# 88__2.net
KiCad netlist of a schematic drawn in Altium Designer
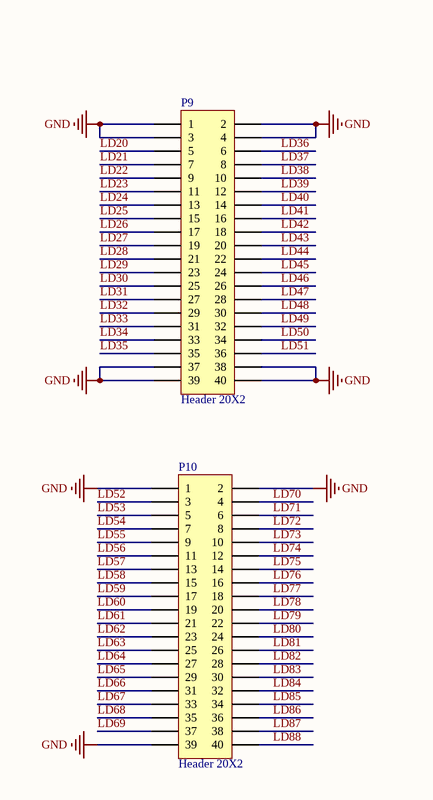
[diagram p0: 88路激光器工程_2.SchDoc, top left]
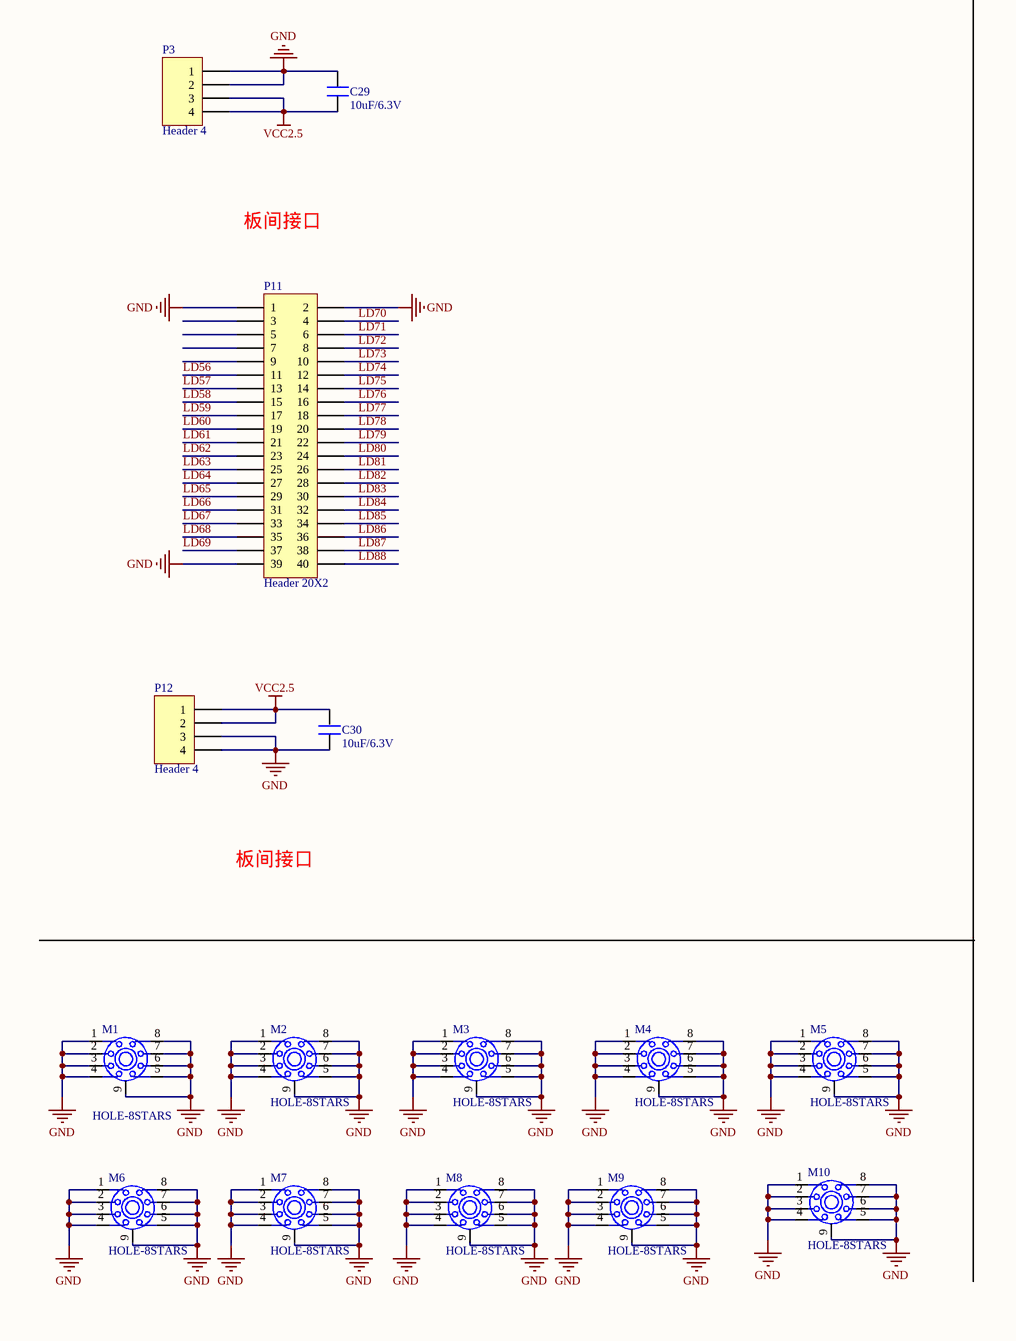
[diagram p1: 88路激光器工程_2.SchDoc, bottom left]
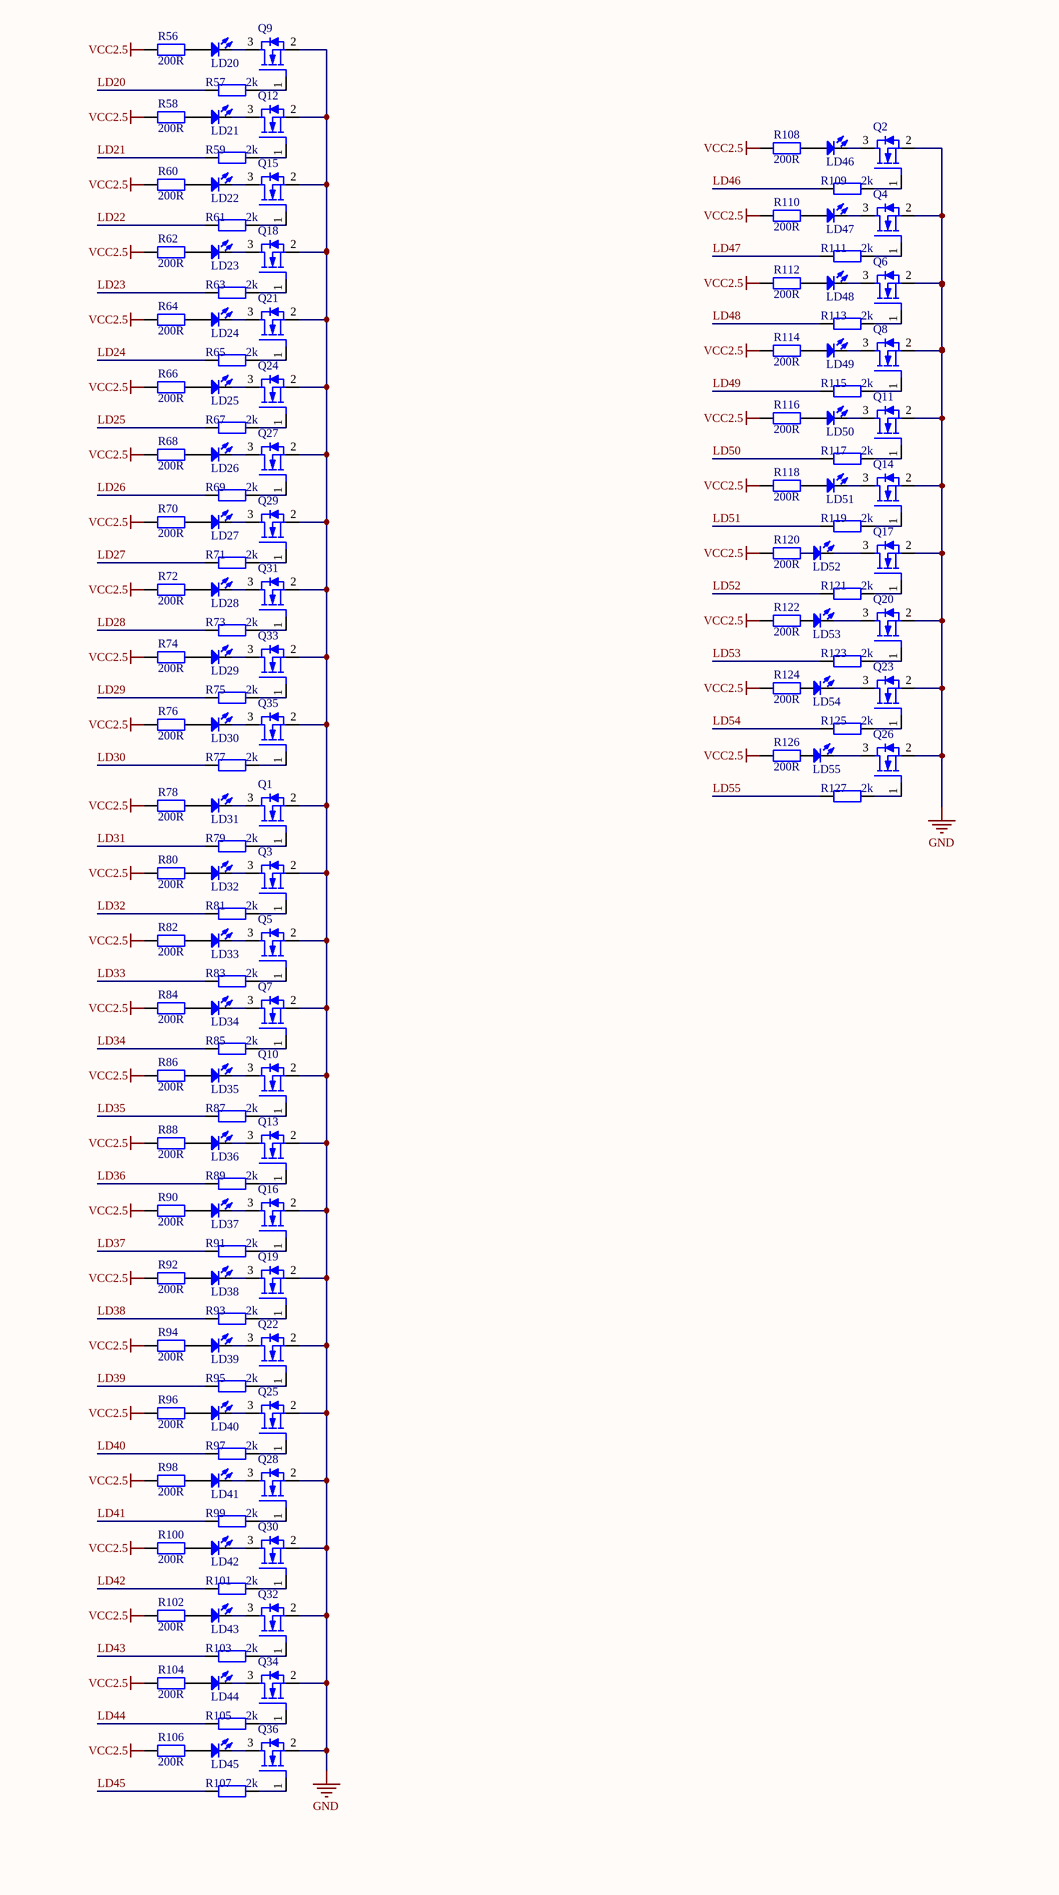
[diagram p2: 88路激光器工程_2.SchDoc, bottom right]

(export (version "E")
  (design (tool "Eeschema 10.0.6"))
  (components
    (comp (ref "C29")
      (value "10uF/6.3V")
      (footprint "C0805")
      (libsource (lib "Explorer STM32F407封装库2") (part "C"))
    )
    (comp (ref "C30")
      (value "10uF/6.3V")
      (footprint "C0805")
      (libsource (lib "Explorer STM32F407封装库2") (part "C"))
    )
    (comp (ref "LD20") (value "LD") (footprint "LD_3P") (libsource (lib "SchLib1") (part "LD")))
    (comp (ref "LD21") (value "LD") (footprint "LD_3P") (libsource (lib "SchLib1") (part "LD")))
    (comp (ref "LD22") (value "LD") (footprint "LD_3P") (libsource (lib "SchLib1") (part "LD")))
    (comp (ref "LD23") (value "LD") (footprint "LD_3P") (libsource (lib "SchLib1") (part "LD")))
    (comp (ref "LD24") (value "LD") (footprint "LD_3P") (libsource (lib "SchLib1") (part "LD")))
    (comp (ref "LD25") (value "LD") (footprint "LD_3P") (libsource (lib "SchLib1") (part "LD")))
    (comp (ref "LD26") (value "LD") (footprint "LD_3P") (libsource (lib "SchLib1") (part "LD")))
    (comp (ref "LD27") (value "LD") (footprint "LD_3P") (libsource (lib "SchLib1") (part "LD")))
    (comp (ref "LD28") (value "LD") (footprint "LD_3P") (libsource (lib "SchLib1") (part "LD")))
    (comp (ref "LD29") (value "LD") (footprint "LD_3P") (libsource (lib "SchLib1") (part "LD")))
    (comp (ref "LD30") (value "LD") (footprint "LD_3P") (libsource (lib "SchLib1") (part "LD")))
    (comp (ref "LD31") (value "LD") (footprint "LD_3P") (libsource (lib "SchLib1") (part "LD")))
    (comp (ref "LD32") (value "LD") (footprint "LD_3P") (libsource (lib "SchLib1") (part "LD")))
    (comp (ref "LD33") (value "LD") (footprint "LD_3P") (libsource (lib "SchLib1") (part "LD")))
    (comp (ref "LD34") (value "LD") (footprint "LD_3P") (libsource (lib "SchLib1") (part "LD")))
    (comp (ref "LD35") (value "LD") (footprint "LD_3P") (libsource (lib "SchLib1") (part "LD")))
    (comp (ref "LD36") (value "LD") (footprint "LD_3P") (libsource (lib "SchLib1") (part "LD")))
    (comp (ref "LD37") (value "LD") (footprint "LD_3P") (libsource (lib "SchLib1") (part "LD")))
    (comp (ref "LD38") (value "LD") (footprint "LD_3P") (libsource (lib "SchLib1") (part "LD")))
    (comp (ref "LD39") (value "LD") (footprint "LD_3P") (libsource (lib "SchLib1") (part "LD")))
    (comp (ref "LD40") (value "LD") (footprint "LD_3P") (libsource (lib "SchLib1") (part "LD")))
    (comp (ref "LD41") (value "LD") (footprint "LD_3P") (libsource (lib "SchLib1") (part "LD")))
    (comp (ref "LD42") (value "LD") (footprint "LD_3P") (libsource (lib "SchLib1") (part "LD")))
    (comp (ref "LD43") (value "LD") (footprint "LD_3P") (libsource (lib "SchLib1") (part "LD")))
    (comp (ref "LD44") (value "LD") (footprint "LD_3P") (libsource (lib "SchLib1") (part "LD")))
    (comp (ref "LD45") (value "LD") (footprint "LD_3P") (libsource (lib "SchLib1") (part "LD")))
    (comp (ref "LD46") (value "LD") (footprint "LD_3P") (libsource (lib "SchLib1") (part "LD")))
    (comp (ref "LD47") (value "LD") (footprint "LD_3P") (libsource (lib "SchLib1") (part "LD")))
    (comp (ref "LD48") (value "LD") (footprint "LD_3P") (libsource (lib "SchLib1") (part "LD")))
    (comp (ref "LD49") (value "LD") (footprint "LD_3P") (libsource (lib "SchLib1") (part "LD")))
    (comp (ref "LD50") (value "LD") (footprint "LD_3P") (libsource (lib "SchLib1") (part "LD")))
    (comp (ref "LD51") (value "LD") (footprint "LD_3P") (libsource (lib "SchLib1") (part "LD")))
    (comp (ref "LD52") (value "LD") (footprint "LD_3P") (libsource (lib "SchLib1") (part "LD")))
    (comp (ref "LD53") (value "LD") (footprint "LD_3P") (libsource (lib "SchLib1") (part "LD")))
    (comp (ref "LD54") (value "LD") (footprint "LD_3P") (libsource (lib "SchLib1") (part "LD")))
    (comp (ref "LD55") (value "LD") (footprint "LD_3P") (libsource (lib "SchLib1") (part "LD")))
    (comp (ref "M1")
      (value "HOLE-8STARS")
      (footprint "HOLE_3MM")
      (libsource (lib "TOF_SCH") (part "HOLE-8STARS"))
    )
    (comp (ref "M2")
      (value "HOLE-8STARS")
      (footprint "HOLE_3MM")
      (libsource (lib "TOF_SCH") (part "HOLE-8STARS"))
    )
    (comp (ref "M3")
      (value "HOLE-8STARS")
      (footprint "HOLE_3MM")
      (libsource (lib "TOF_SCH") (part "HOLE-8STARS"))
    )
    (comp (ref "M4")
      (value "HOLE-8STARS")
      (footprint "HOLE_3MM")
      (libsource (lib "TOF_SCH") (part "HOLE-8STARS"))
    )
    (comp (ref "M5")
      (value "HOLE-8STARS")
      (footprint "HOLE_3MM")
      (libsource (lib "TOF_SCH") (part "HOLE-8STARS"))
    )
    (comp (ref "M6")
      (value "HOLE-8STARS")
      (footprint "HOLE_3MM")
      (libsource (lib "TOF_SCH") (part "HOLE-8STARS"))
    )
    (comp (ref "M7")
      (value "HOLE-8STARS")
      (footprint "HOLE_3MM")
      (libsource (lib "TOF_SCH") (part "HOLE-8STARS"))
    )
    (comp (ref "M8")
      (value "HOLE-8STARS")
      (footprint "HOLE_3MM")
      (libsource (lib "TOF_SCH") (part "HOLE-8STARS"))
    )
    (comp (ref "M9")
      (value "HOLE-8STARS")
      (footprint "HOLE_3MM")
      (libsource (lib "TOF_SCH") (part "HOLE-8STARS"))
    )
    (comp (ref "M10")
      (value "HOLE-8STARS")
      (footprint "HOLE_3MM")
      (libsource (lib "TOF_SCH") (part "HOLE-8STARS"))
    )
    (comp (ref "P3")
      (value "Header 4")
      (footprint "XH2.54MM_4P_立式")
      (description "Header, 4-Pin")
      (fields (field (name "PUBLISHER") "Altium Limited"))
      (libsource (lib "Miscellaneous Connectors") (part "Header 4"))
    )
    (comp (ref "P9")
      (value "Header 20X2")
      (footprint "JATG_2.0mm_2x20P_SMD")
      (description "Header, 20-Pin, Dual row")
      (fields (field (name "PUBLISHER") "Altium Limited"))
      (libsource (lib "Miscellaneous Connectors") (part "Header 20X2"))
    )
    (comp (ref "P10")
      (value "Header 20X2")
      (footprint "JATG_2.0mm_2x20P_SMD")
      (description "Header, 20-Pin, Dual row")
      (fields (field (name "PUBLISHER") "Altium Limited"))
      (libsource (lib "Miscellaneous Connectors") (part "Header 20X2"))
    )
    (comp (ref "P11")
      (value "Header 20X2")
      (footprint "JATG_2.0mm_2x20P_SMD")
      (description "Header, 20-Pin, Dual row")
      (fields (field (name "PUBLISHER") "Altium Limited"))
      (libsource (lib "Miscellaneous Connectors") (part "Header 20X2"))
    )
    (comp (ref "P12")
      (value "Header 4")
      (footprint "XH2.54MM_4P_立式")
      (description "Header, 4-Pin")
      (fields (field (name "PUBLISHER") "Altium Limited"))
      (libsource (lib "Miscellaneous Connectors") (part "Header 4"))
    )
    (comp (ref "Q1") (value "NMOS") (footprint "SOT23-3") (libsource (lib "88路激光器工程") (part "NMOS")))
    (comp (ref "Q2") (value "NMOS") (footprint "SOT23-3") (libsource (lib "88路激光器工程") (part "NMOS")))
    (comp (ref "Q3") (value "NMOS") (footprint "SOT23-3") (libsource (lib "88路激光器工程") (part "NMOS")))
    (comp (ref "Q4") (value "NMOS") (footprint "SOT23-3") (libsource (lib "88路激光器工程") (part "NMOS")))
    (comp (ref "Q5") (value "NMOS") (footprint "SOT23-3") (libsource (lib "88路激光器工程") (part "NMOS")))
    (comp (ref "Q6") (value "NMOS") (footprint "SOT23-3") (libsource (lib "88路激光器工程") (part "NMOS")))
    (comp (ref "Q7") (value "NMOS") (footprint "SOT23-3") (libsource (lib "88路激光器工程") (part "NMOS")))
    (comp (ref "Q8") (value "NMOS") (footprint "SOT23-3") (libsource (lib "88路激光器工程") (part "NMOS")))
    (comp (ref "Q9") (value "NMOS") (footprint "SOT23-3") (libsource (lib "88路激光器工程") (part "NMOS")))
    (comp (ref "Q10") (value "NMOS") (footprint "SOT23-3") (libsource (lib "88路激光器工程") (part "NMOS")))
    (comp (ref "Q11") (value "NMOS") (footprint "SOT23-3") (libsource (lib "88路激光器工程") (part "NMOS")))
    (comp (ref "Q12") (value "NMOS") (footprint "SOT23-3") (libsource (lib "88路激光器工程") (part "NMOS")))
    (comp (ref "Q13") (value "NMOS") (footprint "SOT23-3") (libsource (lib "88路激光器工程") (part "NMOS")))
    (comp (ref "Q14") (value "NMOS") (footprint "SOT23-3") (libsource (lib "88路激光器工程") (part "NMOS")))
    (comp (ref "Q15") (value "NMOS") (footprint "SOT23-3") (libsource (lib "88路激光器工程") (part "NMOS")))
    (comp (ref "Q16") (value "NMOS") (footprint "SOT23-3") (libsource (lib "88路激光器工程") (part "NMOS")))
    (comp (ref "Q17") (value "NMOS") (footprint "SOT23-3") (libsource (lib "88路激光器工程") (part "NMOS")))
    (comp (ref "Q18") (value "NMOS") (footprint "SOT23-3") (libsource (lib "88路激光器工程") (part "NMOS")))
    (comp (ref "Q19") (value "NMOS") (footprint "SOT23-3") (libsource (lib "88路激光器工程") (part "NMOS")))
    (comp (ref "Q20") (value "NMOS") (footprint "SOT23-3") (libsource (lib "88路激光器工程") (part "NMOS")))
    (comp (ref "Q21") (value "NMOS") (footprint "SOT23-3") (libsource (lib "88路激光器工程") (part "NMOS")))
    (comp (ref "Q22") (value "NMOS") (footprint "SOT23-3") (libsource (lib "88路激光器工程") (part "NMOS")))
    (comp (ref "Q23") (value "NMOS") (footprint "SOT23-3") (libsource (lib "88路激光器工程") (part "NMOS")))
    (comp (ref "Q24") (value "NMOS") (footprint "SOT23-3") (libsource (lib "88路激光器工程") (part "NMOS")))
    (comp (ref "Q25") (value "NMOS") (footprint "SOT23-3") (libsource (lib "88路激光器工程") (part "NMOS")))
    (comp (ref "Q26") (value "NMOS") (footprint "SOT23-3") (libsource (lib "88路激光器工程") (part "NMOS")))
    (comp (ref "Q27") (value "NMOS") (footprint "SOT23-3") (libsource (lib "88路激光器工程") (part "NMOS")))
    (comp (ref "Q28") (value "NMOS") (footprint "SOT23-3") (libsource (lib "88路激光器工程") (part "NMOS")))
    (comp (ref "Q29") (value "NMOS") (footprint "SOT23-3") (libsource (lib "88路激光器工程") (part "NMOS")))
    (comp (ref "Q30") (value "NMOS") (footprint "SOT23-3") (libsource (lib "88路激光器工程") (part "NMOS")))
    (comp (ref "Q31") (value "NMOS") (footprint "SOT23-3") (libsource (lib "88路激光器工程") (part "NMOS")))
    (comp (ref "Q32") (value "NMOS") (footprint "SOT23-3") (libsource (lib "88路激光器工程") (part "NMOS")))
    (comp (ref "Q33") (value "NMOS") (footprint "SOT23-3") (libsource (lib "88路激光器工程") (part "NMOS")))
    (comp (ref "Q34") (value "NMOS") (footprint "SOT23-3") (libsource (lib "88路激光器工程") (part "NMOS")))
    (comp (ref "Q35") (value "NMOS") (footprint "SOT23-3") (libsource (lib "88路激光器工程") (part "NMOS")))
    (comp (ref "Q36") (value "NMOS") (footprint "SOT23-3") (libsource (lib "88路激光器工程") (part "NMOS")))
    (comp (ref "R56")
      (value "200R")
      (footprint "R0805")
      (description "Resistor")
      (fields (field (name "PUBLISHER") "Altium Limited"))
      (libsource (lib "Miscellaneous Devices") (part "Res2"))
    )
    (comp (ref "R57")
      (value "2k")
      (footprint "R0805")
      (description "Resistor")
      (fields (field (name "PUBLISHER") "Altium Limited"))
      (libsource (lib "Miscellaneous Devices") (part "Res2"))
    )
    (comp (ref "R58")
      (value "200R")
      (footprint "R0805")
      (description "Resistor")
      (fields (field (name "PUBLISHER") "Altium Limited"))
      (libsource (lib "Miscellaneous Devices") (part "Res2"))
    )
    (comp (ref "R59")
      (value "2k")
      (footprint "R0805")
      (description "Resistor")
      (fields (field (name "PUBLISHER") "Altium Limited"))
      (libsource (lib "Miscellaneous Devices") (part "Res2"))
    )
    (comp (ref "R60")
      (value "200R")
      (footprint "R0805")
      (description "Resistor")
      (fields (field (name "PUBLISHER") "Altium Limited"))
      (libsource (lib "Miscellaneous Devices") (part "Res2"))
    )
    (comp (ref "R61")
      (value "2k")
      (footprint "R0805")
      (description "Resistor")
      (fields (field (name "PUBLISHER") "Altium Limited"))
      (libsource (lib "Miscellaneous Devices") (part "Res2"))
    )
    (comp (ref "R62")
      (value "200R")
      (footprint "R0805")
      (description "Resistor")
      (fields (field (name "PUBLISHER") "Altium Limited"))
      (libsource (lib "Miscellaneous Devices") (part "Res2"))
    )
    (comp (ref "R63")
      (value "2k")
      (footprint "R0805")
      (description "Resistor")
      (fields (field (name "PUBLISHER") "Altium Limited"))
      (libsource (lib "Miscellaneous Devices") (part "Res2"))
    )
    (comp (ref "R64")
      (value "200R")
      (footprint "R0805")
      (description "Resistor")
      (fields (field (name "PUBLISHER") "Altium Limited"))
      (libsource (lib "Miscellaneous Devices") (part "Res2"))
    )
    (comp (ref "R65")
      (value "2k")
      (footprint "R0805")
      (description "Resistor")
      (fields (field (name "PUBLISHER") "Altium Limited"))
      (libsource (lib "Miscellaneous Devices") (part "Res2"))
    )
    (comp (ref "R66")
      (value "200R")
      (footprint "R0805")
      (description "Resistor")
      (fields (field (name "PUBLISHER") "Altium Limited"))
      (libsource (lib "Miscellaneous Devices") (part "Res2"))
    )
    (comp (ref "R67")
      (value "2k")
      (footprint "R0805")
      (description "Resistor")
      (fields (field (name "PUBLISHER") "Altium Limited"))
      (libsource (lib "Miscellaneous Devices") (part "Res2"))
    )
    (comp (ref "R68")
      (value "200R")
      (footprint "R0805")
      (description "Resistor")
      (fields (field (name "PUBLISHER") "Altium Limited"))
      (libsource (lib "Miscellaneous Devices") (part "Res2"))
    )
    (comp (ref "R69")
      (value "2k")
      (footprint "R0805")
      (description "Resistor")
      (fields (field (name "PUBLISHER") "Altium Limited"))
      (libsource (lib "Miscellaneous Devices") (part "Res2"))
    )
    (comp (ref "R70")
      (value "200R")
      (footprint "R0805")
      (description "Resistor")
      (fields (field (name "PUBLISHER") "Altium Limited"))
      (libsource (lib "Miscellaneous Devices") (part "Res2"))
    )
    (comp (ref "R71")
      (value "2k")
      (footprint "R0805")
      (description "Resistor")
      (fields (field (name "PUBLISHER") "Altium Limited"))
      (libsource (lib "Miscellaneous Devices") (part "Res2"))
    )
    (comp (ref "R72")
      (value "200R")
      (footprint "R0805")
      (description "Resistor")
      (fields (field (name "PUBLISHER") "Altium Limited"))
      (libsource (lib "Miscellaneous Devices") (part "Res2"))
    )
    (comp (ref "R73")
      (value "2k")
      (footprint "R0805")
      (description "Resistor")
      (fields (field (name "PUBLISHER") "Altium Limited"))
      (libsource (lib "Miscellaneous Devices") (part "Res2"))
    )
    (comp (ref "R74")
      (value "200R")
      (footprint "R0805")
      (description "Resistor")
      (fields (field (name "PUBLISHER") "Altium Limited"))
      (libsource (lib "Miscellaneous Devices") (part "Res2"))
    )
    (comp (ref "R75")
      (value "2k")
      (footprint "R0805")
      (description "Resistor")
      (fields (field (name "PUBLISHER") "Altium Limited"))
      (libsource (lib "Miscellaneous Devices") (part "Res2"))
    )
    (comp (ref "R76")
      (value "200R")
      (footprint "R0805")
      (description "Resistor")
      (fields (field (name "PUBLISHER") "Altium Limited"))
      (libsource (lib "Miscellaneous Devices") (part "Res2"))
    )
    (comp (ref "R77")
      (value "2k")
      (footprint "R0805")
      (description "Resistor")
      (fields (field (name "PUBLISHER") "Altium Limited"))
      (libsource (lib "Miscellaneous Devices") (part "Res2"))
    )
    (comp (ref "R78")
      (value "200R")
      (footprint "R0805")
      (description "Resistor")
      (fields (field (name "PUBLISHER") "Altium Limited"))
      (libsource (lib "Miscellaneous Devices") (part "Res2"))
    )
    (comp (ref "R79")
      (value "2k")
      (footprint "R0805")
      (description "Resistor")
      (fields (field (name "PUBLISHER") "Altium Limited"))
      (libsource (lib "Miscellaneous Devices") (part "Res2"))
    )
    (comp (ref "R80")
      (value "200R")
      (footprint "R0805")
      (description "Resistor")
      (fields (field (name "PUBLISHER") "Altium Limited"))
      (libsource (lib "Miscellaneous Devices") (part "Res2"))
    )
    (comp (ref "R81")
      (value "2k")
      (footprint "R0805")
      (description "Resistor")
      (fields (field (name "PUBLISHER") "Altium Limited"))
      (libsource (lib "Miscellaneous Devices") (part "Res2"))
    )
    (comp (ref "R82")
      (value "200R")
      (footprint "R0805")
      (description "Resistor")
      (fields (field (name "PUBLISHER") "Altium Limited"))
      (libsource (lib "Miscellaneous Devices") (part "Res2"))
    )
    (comp (ref "R83")
      (value "2k")
      (footprint "R0805")
      (description "Resistor")
      (fields (field (name "PUBLISHER") "Altium Limited"))
      (libsource (lib "Miscellaneous Devices") (part "Res2"))
    )
    (comp (ref "R84")
      (value "200R")
      (footprint "R0805")
      (description "Resistor")
      (fields (field (name "PUBLISHER") "Altium Limited"))
      (libsource (lib "Miscellaneous Devices") (part "Res2"))
    )
    (comp (ref "R85")
      (value "2k")
      (footprint "R0805")
      (description "Resistor")
      (fields (field (name "PUBLISHER") "Altium Limited"))
      (libsource (lib "Miscellaneous Devices") (part "Res2"))
    )
    (comp (ref "R86")
      (value "200R")
      (footprint "R0805")
      (description "Resistor")
      (fields (field (name "PUBLISHER") "Altium Limited"))
      (libsource (lib "Miscellaneous Devices") (part "Res2"))
    )
    (comp (ref "R87")
      (value "2k")
      (footprint "R0805")
      (description "Resistor")
      (fields (field (name "PUBLISHER") "Altium Limited"))
      (libsource (lib "Miscellaneous Devices") (part "Res2"))
    )
    (comp (ref "R88")
      (value "200R")
      (footprint "R0805")
      (description "Resistor")
      (fields (field (name "PUBLISHER") "Altium Limited"))
      (libsource (lib "Miscellaneous Devices") (part "Res2"))
    )
    (comp (ref "R89")
      (value "2k")
      (footprint "R0805")
      (description "Resistor")
      (fields (field (name "PUBLISHER") "Altium Limited"))
      (libsource (lib "Miscellaneous Devices") (part "Res2"))
    )
    (comp (ref "R90")
      (value "200R")
      (footprint "R0805")
      (description "Resistor")
      (fields (field (name "PUBLISHER") "Altium Limited"))
      (libsource (lib "Miscellaneous Devices") (part "Res2"))
    )
    (comp (ref "R91")
      (value "2k")
      (footprint "R0805")
      (description "Resistor")
      (fields (field (name "PUBLISHER") "Altium Limited"))
      (libsource (lib "Miscellaneous Devices") (part "Res2"))
    )
    (comp (ref "R92")
      (value "200R")
      (footprint "R0805")
      (description "Resistor")
      (fields (field (name "PUBLISHER") "Altium Limited"))
      (libsource (lib "Miscellaneous Devices") (part "Res2"))
    )
    (comp (ref "R93")
      (value "2k")
      (footprint "R0805")
      (description "Resistor")
      (fields (field (name "PUBLISHER") "Altium Limited"))
      (libsource (lib "Miscellaneous Devices") (part "Res2"))
    )
    (comp (ref "R94")
      (value "200R")
      (footprint "R0805")
      (description "Resistor")
      (fields (field (name "PUBLISHER") "Altium Limited"))
      (libsource (lib "Miscellaneous Devices") (part "Res2"))
    )
    (comp (ref "R95")
      (value "2k")
      (footprint "R0805")
      (description "Resistor")
      (fields (field (name "PUBLISHER") "Altium Limited"))
      (libsource (lib "Miscellaneous Devices") (part "Res2"))
    )
    (comp (ref "R96")
      (value "200R")
      (footprint "R0805")
      (description "Resistor")
      (fields (field (name "PUBLISHER") "Altium Limited"))
      (libsource (lib "Miscellaneous Devices") (part "Res2"))
    )
    (comp (ref "R97")
      (value "2k")
      (footprint "R0805")
      (description "Resistor")
      (fields (field (name "PUBLISHER") "Altium Limited"))
      (libsource (lib "Miscellaneous Devices") (part "Res2"))
    )
    (comp (ref "R98")
      (value "200R")
      (footprint "R0805")
      (description "Resistor")
      (fields (field (name "PUBLISHER") "Altium Limited"))
      (libsource (lib "Miscellaneous Devices") (part "Res2"))
    )
    (comp (ref "R99")
      (value "2k")
      (footprint "R0805")
      (description "Resistor")
      (fields (field (name "PUBLISHER") "Altium Limited"))
      (libsource (lib "Miscellaneous Devices") (part "Res2"))
    )
    (comp (ref "R100")
      (value "200R")
      (footprint "R0805")
      (description "Resistor")
      (fields (field (name "PUBLISHER") "Altium Limited"))
      (libsource (lib "Miscellaneous Devices") (part "Res2"))
    )
    (comp (ref "R101")
      (value "2k")
      (footprint "R0805")
      (description "Resistor")
      (fields (field (name "PUBLISHER") "Altium Limited"))
      (libsource (lib "Miscellaneous Devices") (part "Res2"))
    )
    (comp (ref "R102")
      (value "200R")
      (footprint "R0805")
      (description "Resistor")
      (fields (field (name "PUBLISHER") "Altium Limited"))
      (libsource (lib "Miscellaneous Devices") (part "Res2"))
    )
    (comp (ref "R103")
      (value "2k")
      (footprint "R0805")
      (description "Resistor")
      (fields (field (name "PUBLISHER") "Altium Limited"))
      (libsource (lib "Miscellaneous Devices") (part "Res2"))
    )
    (comp (ref "R104")
      (value "200R")
      (footprint "R0805")
      (description "Resistor")
      (fields (field (name "PUBLISHER") "Altium Limited"))
      (libsource (lib "Miscellaneous Devices") (part "Res2"))
    )
    (comp (ref "R105")
      (value "2k")
      (footprint "R0805")
      (description "Resistor")
      (fields (field (name "PUBLISHER") "Altium Limited"))
      (libsource (lib "Miscellaneous Devices") (part "Res2"))
    )
    (comp (ref "R106")
      (value "200R")
      (footprint "R0805")
      (description "Resistor")
      (fields (field (name "PUBLISHER") "Altium Limited"))
      (libsource (lib "Miscellaneous Devices") (part "Res2"))
    )
    (comp (ref "R107")
      (value "2k")
      (footprint "R0805")
      (description "Resistor")
      (fields (field (name "PUBLISHER") "Altium Limited"))
      (libsource (lib "Miscellaneous Devices") (part "Res2"))
    )
    (comp (ref "R108")
      (value "200R")
      (footprint "R0805")
      (description "Resistor")
      (fields (field (name "PUBLISHER") "Altium Limited"))
      (libsource (lib "Miscellaneous Devices") (part "Res2"))
    )
    (comp (ref "R109")
      (value "2k")
      (footprint "R0805")
      (description "Resistor")
      (fields (field (name "PUBLISHER") "Altium Limited"))
      (libsource (lib "Miscellaneous Devices") (part "Res2"))
    )
    (comp (ref "R110")
      (value "200R")
      (footprint "R0805")
      (description "Resistor")
      (fields (field (name "PUBLISHER") "Altium Limited"))
      (libsource (lib "Miscellaneous Devices") (part "Res2"))
    )
    (comp (ref "R111")
      (value "2k")
      (footprint "R0805")
      (description "Resistor")
      (fields (field (name "PUBLISHER") "Altium Limited"))
      (libsource (lib "Miscellaneous Devices") (part "Res2"))
    )
    (comp (ref "R112")
      (value "200R")
      (footprint "R0805")
      (description "Resistor")
      (fields (field (name "PUBLISHER") "Altium Limited"))
      (libsource (lib "Miscellaneous Devices") (part "Res2"))
    )
    (comp (ref "R113")
      (value "2k")
      (footprint "R0805")
      (description "Resistor")
      (fields (field (name "PUBLISHER") "Altium Limited"))
      (libsource (lib "Miscellaneous Devices") (part "Res2"))
    )
    (comp (ref "R114")
      (value "200R")
      (footprint "R0805")
      (description "Resistor")
      (fields (field (name "PUBLISHER") "Altium Limited"))
      (libsource (lib "Miscellaneous Devices") (part "Res2"))
    )
    (comp (ref "R115")
      (value "2k")
      (footprint "R0805")
      (description "Resistor")
      (fields (field (name "PUBLISHER") "Altium Limited"))
      (libsource (lib "Miscellaneous Devices") (part "Res2"))
    )
    (comp (ref "R116")
      (value "200R")
      (footprint "R0805")
      (description "Resistor")
      (fields (field (name "PUBLISHER") "Altium Limited"))
      (libsource (lib "Miscellaneous Devices") (part "Res2"))
    )
    (comp (ref "R117")
      (value "2k")
      (footprint "R0805")
      (description "Resistor")
      (fields (field (name "PUBLISHER") "Altium Limited"))
      (libsource (lib "Miscellaneous Devices") (part "Res2"))
    )
    (comp (ref "R118")
      (value "200R")
      (footprint "R0805")
      (description "Resistor")
      (fields (field (name "PUBLISHER") "Altium Limited"))
      (libsource (lib "Miscellaneous Devices") (part "Res2"))
    )
    (comp (ref "R119")
      (value "2k")
      (footprint "R0805")
      (description "Resistor")
      (fields (field (name "PUBLISHER") "Altium Limited"))
      (libsource (lib "Miscellaneous Devices") (part "Res2"))
    )
    (comp (ref "R120")
      (value "200R")
      (footprint "R0805")
      (description "Resistor")
      (fields (field (name "PUBLISHER") "Altium Limited"))
      (libsource (lib "Miscellaneous Devices") (part "Res2"))
    )
    (comp (ref "R121")
      (value "2k")
      (footprint "R0805")
      (description "Resistor")
      (fields (field (name "PUBLISHER") "Altium Limited"))
      (libsource (lib "Miscellaneous Devices") (part "Res2"))
    )
    (comp (ref "R122")
      (value "200R")
      (footprint "R0805")
      (description "Resistor")
      (fields (field (name "PUBLISHER") "Altium Limited"))
      (libsource (lib "Miscellaneous Devices") (part "Res2"))
    )
    (comp (ref "R123")
      (value "2k")
      (footprint "R0805")
      (description "Resistor")
      (fields (field (name "PUBLISHER") "Altium Limited"))
      (libsource (lib "Miscellaneous Devices") (part "Res2"))
    )
    (comp (ref "R124")
      (value "200R")
      (footprint "R0805")
      (description "Resistor")
      (fields (field (name "PUBLISHER") "Altium Limited"))
      (libsource (lib "Miscellaneous Devices") (part "Res2"))
    )
    (comp (ref "R125")
      (value "2k")
      (footprint "R0805")
      (description "Resistor")
      (fields (field (name "PUBLISHER") "Altium Limited"))
      (libsource (lib "Miscellaneous Devices") (part "Res2"))
    )
    (comp (ref "R126")
      (value "200R")
      (footprint "R0805")
      (description "Resistor")
      (fields (field (name "PUBLISHER") "Altium Limited"))
      (libsource (lib "Miscellaneous Devices") (part "Res2"))
    )
    (comp (ref "R127")
      (value "2k")
      (footprint "R0805")
      (description "Resistor")
      (fields (field (name "PUBLISHER") "Altium Limited"))
      (libsource (lib "Miscellaneous Devices") (part "Res2"))
    )
  )
  (nets
    (net (code "1") (name "/LD20") (class "Default")
      (node (ref "P9") (pin "5") (pinfunction "5_5") (pintype "passive"))
      (node (ref "R57") (pin "2") (pinfunction "2_2") (pintype "passive"))
    )
    (net (code "2") (name "/LD21") (class "Default")
      (node (ref "P9") (pin "7") (pinfunction "7_7") (pintype "passive"))
      (node (ref "R59") (pin "2") (pinfunction "2_2") (pintype "passive"))
    )
    (net (code "3") (name "/LD22") (class "Default")
      (node (ref "P9") (pin "9") (pinfunction "9_9") (pintype "passive"))
      (node (ref "R61") (pin "2") (pinfunction "2_2") (pintype "passive"))
    )
    (net (code "4") (name "/LD23") (class "Default")
      (node (ref "P9") (pin "11") (pinfunction "11_11") (pintype "passive"))
      (node (ref "R63") (pin "2") (pinfunction "2_2") (pintype "passive"))
    )
    (net (code "5") (name "/LD24") (class "Default")
      (node (ref "P9") (pin "13") (pinfunction "13_13") (pintype "passive"))
      (node (ref "R65") (pin "2") (pinfunction "2_2") (pintype "passive"))
    )
    (net (code "6") (name "/LD25") (class "Default")
      (node (ref "P9") (pin "15") (pinfunction "15_15") (pintype "passive"))
      (node (ref "R67") (pin "2") (pinfunction "2_2") (pintype "passive"))
    )
    (net (code "7") (name "/LD26") (class "Default")
      (node (ref "P9") (pin "17") (pinfunction "17_17") (pintype "passive"))
      (node (ref "R69") (pin "2") (pinfunction "2_2") (pintype "passive"))
    )
    (net (code "8") (name "/LD27") (class "Default")
      (node (ref "P9") (pin "19") (pinfunction "19_19") (pintype "passive"))
      (node (ref "R71") (pin "2") (pinfunction "2_2") (pintype "passive"))
    )
    (net (code "9") (name "/LD28") (class "Default")
      (node (ref "P9") (pin "21") (pinfunction "21_21") (pintype "passive"))
      (node (ref "R73") (pin "2") (pinfunction "2_2") (pintype "passive"))
    )
    (net (code "10") (name "/LD29") (class "Default")
      (node (ref "P9") (pin "23") (pinfunction "23_23") (pintype "passive"))
      (node (ref "R75") (pin "2") (pinfunction "2_2") (pintype "passive"))
    )
    (net (code "11") (name "/LD30") (class "Default")
      (node (ref "P9") (pin "25") (pinfunction "25_25") (pintype "passive"))
      (node (ref "R77") (pin "2") (pinfunction "2_2") (pintype "passive"))
    )
    (net (code "12") (name "/LD31") (class "Default")
      (node (ref "P9") (pin "27") (pinfunction "27_27") (pintype "passive"))
      (node (ref "R79") (pin "2") (pinfunction "2_2") (pintype "passive"))
    )
    (net (code "13") (name "/LD32") (class "Default")
      (node (ref "P9") (pin "29") (pinfunction "29_29") (pintype "passive"))
      (node (ref "R81") (pin "2") (pinfunction "2_2") (pintype "passive"))
    )
    (net (code "14") (name "/LD33") (class "Default")
      (node (ref "P9") (pin "31") (pinfunction "31_31") (pintype "passive"))
      (node (ref "R83") (pin "2") (pinfunction "2_2") (pintype "passive"))
    )
    (net (code "15") (name "/LD34") (class "Default")
      (node (ref "P9") (pin "33") (pinfunction "33_33") (pintype "passive"))
      (node (ref "R85") (pin "2") (pinfunction "2_2") (pintype "passive"))
    )
    (net (code "16") (name "/LD35") (class "Default")
      (node (ref "P9") (pin "35") (pinfunction "35_35") (pintype "passive"))
      (node (ref "R87") (pin "2") (pinfunction "2_2") (pintype "passive"))
    )
    (net (code "17") (name "/LD36") (class "Default")
      (node (ref "P9") (pin "6") (pinfunction "6_6") (pintype "passive"))
      (node (ref "R89") (pin "2") (pinfunction "2_2") (pintype "passive"))
    )
    (net (code "18") (name "/LD37") (class "Default")
      (node (ref "P9") (pin "8") (pinfunction "8_8") (pintype "passive"))
      (node (ref "R91") (pin "2") (pinfunction "2_2") (pintype "passive"))
    )
    (net (code "19") (name "/LD38") (class "Default")
      (node (ref "P9") (pin "10") (pinfunction "10_10") (pintype "passive"))
      (node (ref "R93") (pin "2") (pinfunction "2_2") (pintype "passive"))
    )
    (net (code "20") (name "/LD39") (class "Default")
      (node (ref "P9") (pin "12") (pinfunction "12_12") (pintype "passive"))
      (node (ref "R95") (pin "2") (pinfunction "2_2") (pintype "passive"))
    )
    (net (code "21") (name "/LD40") (class "Default")
      (node (ref "P9") (pin "14") (pinfunction "14_14") (pintype "passive"))
      (node (ref "R97") (pin "2") (pinfunction "2_2") (pintype "passive"))
    )
    (net (code "22") (name "/LD41") (class "Default")
      (node (ref "P9") (pin "16") (pinfunction "16_16") (pintype "passive"))
      (node (ref "R99") (pin "2") (pinfunction "2_2") (pintype "passive"))
    )
    (net (code "23") (name "/LD42") (class "Default")
      (node (ref "P9") (pin "18") (pinfunction "18_18") (pintype "passive"))
      (node (ref "R101") (pin "2") (pinfunction "2_2") (pintype "passive"))
    )
    (net (code "24") (name "/LD43") (class "Default")
      (node (ref "P9") (pin "20") (pinfunction "20_20") (pintype "passive"))
      (node (ref "R103") (pin "2") (pinfunction "2_2") (pintype "passive"))
    )
    (net (code "25") (name "/LD44") (class "Default")
      (node (ref "P9") (pin "22") (pinfunction "22_22") (pintype "passive"))
      (node (ref "R105") (pin "2") (pinfunction "2_2") (pintype "passive"))
    )
    (net (code "26") (name "/LD45") (class "Default")
      (node (ref "P9") (pin "24") (pinfunction "24_24") (pintype "passive"))
      (node (ref "R107") (pin "2") (pinfunction "2_2") (pintype "passive"))
    )
    (net (code "27") (name "/LD46") (class "Default")
      (node (ref "P9") (pin "26") (pinfunction "26_26") (pintype "passive"))
      (node (ref "R109") (pin "2") (pinfunction "2_2") (pintype "passive"))
    )
    (net (code "28") (name "/LD47") (class "Default")
      (node (ref "P9") (pin "28") (pinfunction "28_28") (pintype "passive"))
      (node (ref "R111") (pin "2") (pinfunction "2_2") (pintype "passive"))
    )
    (net (code "29") (name "/LD48") (class "Default")
      (node (ref "P9") (pin "30") (pinfunction "30_30") (pintype "passive"))
      (node (ref "R113") (pin "2") (pinfunction "2_2") (pintype "passive"))
    )
    (net (code "30") (name "/LD49") (class "Default")
      (node (ref "P9") (pin "32") (pinfunction "32_32") (pintype "passive"))
      (node (ref "R115") (pin "2") (pinfunction "2_2") (pintype "passive"))
    )
    (net (code "31") (name "/LD50") (class "Default")
      (node (ref "P9") (pin "34") (pinfunction "34_34") (pintype "passive"))
      (node (ref "R117") (pin "2") (pinfunction "2_2") (pintype "passive"))
    )
    (net (code "32") (name "/LD51") (class "Default")
      (node (ref "P9") (pin "36") (pinfunction "36_36") (pintype "passive"))
      (node (ref "R119") (pin "2") (pinfunction "2_2") (pintype "passive"))
    )
    (net (code "33") (name "/LD52") (class "Default")
      (node (ref "P10") (pin "3") (pinfunction "3_3") (pintype "passive"))
      (node (ref "R121") (pin "2") (pinfunction "2_2") (pintype "passive"))
    )
    (net (code "34") (name "/LD53") (class "Default")
      (node (ref "P10") (pin "5") (pinfunction "5_5") (pintype "passive"))
      (node (ref "R123") (pin "2") (pinfunction "2_2") (pintype "passive"))
    )
    (net (code "35") (name "/LD54") (class "Default")
      (node (ref "P10") (pin "7") (pinfunction "7_7") (pintype "passive"))
      (node (ref "R125") (pin "2") (pinfunction "2_2") (pintype "passive"))
    )
    (net (code "36") (name "/LD55") (class "Default")
      (node (ref "P10") (pin "9") (pinfunction "9_9") (pintype "passive"))
      (node (ref "R127") (pin "2") (pinfunction "2_2") (pintype "passive"))
    )
    (net (code "37") (name "/LD56") (class "Default")
      (node (ref "P10") (pin "11") (pinfunction "11_11") (pintype "passive"))
      (node (ref "P11") (pin "11") (pinfunction "11_11") (pintype "passive"))
    )
    (net (code "38") (name "/LD57") (class "Default")
      (node (ref "P10") (pin "13") (pinfunction "13_13") (pintype "passive"))
      (node (ref "P11") (pin "13") (pinfunction "13_13") (pintype "passive"))
    )
    (net (code "39") (name "/LD58") (class "Default")
      (node (ref "P10") (pin "15") (pinfunction "15_15") (pintype "passive"))
      (node (ref "P11") (pin "15") (pinfunction "15_15") (pintype "passive"))
    )
    (net (code "40") (name "/LD59") (class "Default")
      (node (ref "P10") (pin "17") (pinfunction "17_17") (pintype "passive"))
      (node (ref "P11") (pin "17") (pinfunction "17_17") (pintype "passive"))
    )
    (net (code "41") (name "/LD60") (class "Default")
      (node (ref "P10") (pin "19") (pinfunction "19_19") (pintype "passive"))
      (node (ref "P11") (pin "19") (pinfunction "19_19") (pintype "passive"))
    )
    (net (code "42") (name "/LD61") (class "Default")
      (node (ref "P10") (pin "21") (pinfunction "21_21") (pintype "passive"))
      (node (ref "P11") (pin "21") (pinfunction "21_21") (pintype "passive"))
    )
    (net (code "43") (name "/LD62") (class "Default")
      (node (ref "P10") (pin "23") (pinfunction "23_23") (pintype "passive"))
      (node (ref "P11") (pin "23") (pinfunction "23_23") (pintype "passive"))
    )
    (net (code "44") (name "/LD63") (class "Default")
      (node (ref "P10") (pin "25") (pinfunction "25_25") (pintype "passive"))
      (node (ref "P11") (pin "25") (pinfunction "25_25") (pintype "passive"))
    )
    (net (code "45") (name "/LD64") (class "Default")
      (node (ref "P10") (pin "27") (pinfunction "27_27") (pintype "passive"))
      (node (ref "P11") (pin "27") (pinfunction "27_27") (pintype "passive"))
    )
    (net (code "46") (name "/LD65") (class "Default")
      (node (ref "P10") (pin "29") (pinfunction "29_29") (pintype "passive"))
      (node (ref "P11") (pin "29") (pinfunction "29_29") (pintype "passive"))
    )
    (net (code "47") (name "/LD66") (class "Default")
      (node (ref "P10") (pin "31") (pinfunction "31_31") (pintype "passive"))
      (node (ref "P11") (pin "31") (pinfunction "31_31") (pintype "passive"))
    )
    (net (code "48") (name "/LD67") (class "Default")
      (node (ref "P10") (pin "33") (pinfunction "33_33") (pintype "passive"))
      (node (ref "P11") (pin "33") (pinfunction "33_33") (pintype "passive"))
    )
    (net (code "49") (name "/LD68") (class "Default")
      (node (ref "P10") (pin "35") (pinfunction "35_35") (pintype "passive"))
      (node (ref "P11") (pin "35") (pinfunction "35_35") (pintype "passive"))
    )
    (net (code "50") (name "/LD69") (class "Default")
      (node (ref "P10") (pin "37") (pinfunction "37_37") (pintype "passive"))
      (node (ref "P11") (pin "37") (pinfunction "37_37") (pintype "passive"))
    )
    (net (code "51") (name "/LD70") (class "Default")
      (node (ref "P10") (pin "4") (pinfunction "4_4") (pintype "passive"))
      (node (ref "P11") (pin "4") (pinfunction "4_4") (pintype "passive"))
    )
    (net (code "52") (name "/LD71") (class "Default")
      (node (ref "P10") (pin "6") (pinfunction "6_6") (pintype "passive"))
      (node (ref "P11") (pin "6") (pinfunction "6_6") (pintype "passive"))
    )
    (net (code "53") (name "/LD72") (class "Default")
      (node (ref "P10") (pin "8") (pinfunction "8_8") (pintype "passive"))
      (node (ref "P11") (pin "8") (pinfunction "8_8") (pintype "passive"))
    )
    (net (code "54") (name "/LD73") (class "Default")
      (node (ref "P10") (pin "10") (pinfunction "10_10") (pintype "passive"))
      (node (ref "P11") (pin "10") (pinfunction "10_10") (pintype "passive"))
    )
    (net (code "55") (name "/LD74") (class "Default")
      (node (ref "P10") (pin "12") (pinfunction "12_12") (pintype "passive"))
      (node (ref "P11") (pin "12") (pinfunction "12_12") (pintype "passive"))
    )
    (net (code "56") (name "/LD75") (class "Default")
      (node (ref "P10") (pin "14") (pinfunction "14_14") (pintype "passive"))
      (node (ref "P11") (pin "14") (pinfunction "14_14") (pintype "passive"))
    )
    (net (code "57") (name "/LD76") (class "Default")
      (node (ref "P10") (pin "16") (pinfunction "16_16") (pintype "passive"))
      (node (ref "P11") (pin "16") (pinfunction "16_16") (pintype "passive"))
    )
    (net (code "58") (name "/LD77") (class "Default")
      (node (ref "P10") (pin "18") (pinfunction "18_18") (pintype "passive"))
      (node (ref "P11") (pin "18") (pinfunction "18_18") (pintype "passive"))
    )
    (net (code "59") (name "/LD78") (class "Default")
      (node (ref "P10") (pin "20") (pinfunction "20_20") (pintype "passive"))
      (node (ref "P11") (pin "20") (pinfunction "20_20") (pintype "passive"))
    )
    (net (code "60") (name "/LD79") (class "Default")
      (node (ref "P10") (pin "22") (pinfunction "22_22") (pintype "passive"))
      (node (ref "P11") (pin "22") (pinfunction "22_22") (pintype "passive"))
    )
    (net (code "61") (name "/LD80") (class "Default")
      (node (ref "P10") (pin "24") (pinfunction "24_24") (pintype "passive"))
      (node (ref "P11") (pin "24") (pinfunction "24_24") (pintype "passive"))
    )
    (net (code "62") (name "/LD81") (class "Default")
      (node (ref "P10") (pin "26") (pinfunction "26_26") (pintype "passive"))
      (node (ref "P11") (pin "26") (pinfunction "26_26") (pintype "passive"))
    )
    (net (code "63") (name "/LD82") (class "Default")
      (node (ref "P10") (pin "28") (pinfunction "28_28") (pintype "passive"))
      (node (ref "P11") (pin "28") (pinfunction "28_28") (pintype "passive"))
    )
    (net (code "64") (name "/LD83") (class "Default")
      (node (ref "P10") (pin "30") (pinfunction "30_30") (pintype "passive"))
      (node (ref "P11") (pin "30") (pinfunction "30_30") (pintype "passive"))
    )
    (net (code "65") (name "/LD84") (class "Default")
      (node (ref "P10") (pin "32") (pinfunction "32_32") (pintype "passive"))
      (node (ref "P11") (pin "32") (pinfunction "32_32") (pintype "passive"))
    )
    (net (code "66") (name "/LD85") (class "Default")
      (node (ref "P10") (pin "34") (pinfunction "34_34") (pintype "passive"))
      (node (ref "P11") (pin "34") (pinfunction "34_34") (pintype "passive"))
    )
    (net (code "67") (name "/LD86") (class "Default")
      (node (ref "P10") (pin "36") (pinfunction "36_36") (pintype "passive"))
      (node (ref "P11") (pin "36") (pinfunction "36_36") (pintype "passive"))
    )
    (net (code "68") (name "/LD87") (class "Default")
      (node (ref "P10") (pin "38") (pinfunction "38_38") (pintype "passive"))
      (node (ref "P11") (pin "38") (pinfunction "38_38") (pintype "passive"))
    )
    (net (code "69") (name "/LD88") (class "Default")
      (node (ref "P10") (pin "40") (pinfunction "40_40") (pintype "passive"))
      (node (ref "P11") (pin "40") (pinfunction "40_40") (pintype "passive"))
    )
    (net (code "70") (name "GND") (class "Default")
      (node (ref "C29") (pin "2") (pintype "passive"))
      (node (ref "C30") (pin "1") (pintype "passive"))
      (node (ref "M1") (pin "1") (pinfunction "1_1") (pintype "passive"))
      (node (ref "M1") (pin "2") (pinfunction "2_2") (pintype "passive"))
      (node (ref "M1") (pin "3") (pinfunction "3_3") (pintype "passive"))
      (node (ref "M1") (pin "4") (pinfunction "4_4") (pintype "passive"))
      (node (ref "M1") (pin "5") (pinfunction "5_5") (pintype "passive"))
      (node (ref "M1") (pin "6") (pinfunction "6_6") (pintype "passive"))
      (node (ref "M1") (pin "7") (pinfunction "7_7") (pintype "passive"))
      (node (ref "M1") (pin "8") (pinfunction "8_8") (pintype "passive"))
      (node (ref "M1") (pin "9") (pinfunction "9_9") (pintype "passive"))
      (node (ref "M10") (pin "1") (pinfunction "1_1") (pintype "passive"))
      (node (ref "M10") (pin "2") (pinfunction "2_2") (pintype "passive"))
      (node (ref "M10") (pin "3") (pinfunction "3_3") (pintype "passive"))
      (node (ref "M10") (pin "4") (pinfunction "4_4") (pintype "passive"))
      (node (ref "M10") (pin "5") (pinfunction "5_5") (pintype "passive"))
      (node (ref "M10") (pin "6") (pinfunction "6_6") (pintype "passive"))
      (node (ref "M10") (pin "7") (pinfunction "7_7") (pintype "passive"))
      (node (ref "M10") (pin "8") (pinfunction "8_8") (pintype "passive"))
      (node (ref "M10") (pin "9") (pinfunction "9_9") (pintype "passive"))
      (node (ref "M2") (pin "1") (pinfunction "1_1") (pintype "passive"))
      (node (ref "M2") (pin "2") (pinfunction "2_2") (pintype "passive"))
      (node (ref "M2") (pin "3") (pinfunction "3_3") (pintype "passive"))
      (node (ref "M2") (pin "4") (pinfunction "4_4") (pintype "passive"))
      (node (ref "M2") (pin "5") (pinfunction "5_5") (pintype "passive"))
      (node (ref "M2") (pin "6") (pinfunction "6_6") (pintype "passive"))
      (node (ref "M2") (pin "7") (pinfunction "7_7") (pintype "passive"))
      (node (ref "M2") (pin "8") (pinfunction "8_8") (pintype "passive"))
      (node (ref "M2") (pin "9") (pinfunction "9_9") (pintype "passive"))
      (node (ref "M3") (pin "1") (pinfunction "1_1") (pintype "passive"))
      (node (ref "M3") (pin "2") (pinfunction "2_2") (pintype "passive"))
      (node (ref "M3") (pin "3") (pinfunction "3_3") (pintype "passive"))
      (node (ref "M3") (pin "4") (pinfunction "4_4") (pintype "passive"))
      (node (ref "M3") (pin "5") (pinfunction "5_5") (pintype "passive"))
      (node (ref "M3") (pin "6") (pinfunction "6_6") (pintype "passive"))
      (node (ref "M3") (pin "7") (pinfunction "7_7") (pintype "passive"))
      (node (ref "M3") (pin "8") (pinfunction "8_8") (pintype "passive"))
      (node (ref "M3") (pin "9") (pinfunction "9_9") (pintype "passive"))
      (node (ref "M4") (pin "1") (pinfunction "1_1") (pintype "passive"))
      (node (ref "M4") (pin "2") (pinfunction "2_2") (pintype "passive"))
      (node (ref "M4") (pin "3") (pinfunction "3_3") (pintype "passive"))
      (node (ref "M4") (pin "4") (pinfunction "4_4") (pintype "passive"))
      (node (ref "M4") (pin "5") (pinfunction "5_5") (pintype "passive"))
      (node (ref "M4") (pin "6") (pinfunction "6_6") (pintype "passive"))
      (node (ref "M4") (pin "7") (pinfunction "7_7") (pintype "passive"))
      (node (ref "M4") (pin "8") (pinfunction "8_8") (pintype "passive"))
      (node (ref "M4") (pin "9") (pinfunction "9_9") (pintype "passive"))
      (node (ref "M5") (pin "1") (pinfunction "1_1") (pintype "passive"))
      (node (ref "M5") (pin "2") (pinfunction "2_2") (pintype "passive"))
      (node (ref "M5") (pin "3") (pinfunction "3_3") (pintype "passive"))
      (node (ref "M5") (pin "4") (pinfunction "4_4") (pintype "passive"))
      (node (ref "M5") (pin "5") (pinfunction "5_5") (pintype "passive"))
      (node (ref "M5") (pin "6") (pinfunction "6_6") (pintype "passive"))
      (node (ref "M5") (pin "7") (pinfunction "7_7") (pintype "passive"))
      (node (ref "M5") (pin "8") (pinfunction "8_8") (pintype "passive"))
      (node (ref "M5") (pin "9") (pinfunction "9_9") (pintype "passive"))
      (node (ref "M6") (pin "1") (pinfunction "1_1") (pintype "passive"))
      (node (ref "M6") (pin "2") (pinfunction "2_2") (pintype "passive"))
      (node (ref "M6") (pin "3") (pinfunction "3_3") (pintype "passive"))
      (node (ref "M6") (pin "4") (pinfunction "4_4") (pintype "passive"))
      (node (ref "M6") (pin "5") (pinfunction "5_5") (pintype "passive"))
      (node (ref "M6") (pin "6") (pinfunction "6_6") (pintype "passive"))
      (node (ref "M6") (pin "7") (pinfunction "7_7") (pintype "passive"))
      (node (ref "M6") (pin "8") (pinfunction "8_8") (pintype "passive"))
      (node (ref "M6") (pin "9") (pinfunction "9_9") (pintype "passive"))
      (node (ref "M7") (pin "1") (pinfunction "1_1") (pintype "passive"))
      (node (ref "M7") (pin "2") (pinfunction "2_2") (pintype "passive"))
      (node (ref "M7") (pin "3") (pinfunction "3_3") (pintype "passive"))
      (node (ref "M7") (pin "4") (pinfunction "4_4") (pintype "passive"))
      (node (ref "M7") (pin "5") (pinfunction "5_5") (pintype "passive"))
      (node (ref "M7") (pin "6") (pinfunction "6_6") (pintype "passive"))
      (node (ref "M7") (pin "7") (pinfunction "7_7") (pintype "passive"))
      (node (ref "M7") (pin "8") (pinfunction "8_8") (pintype "passive"))
      (node (ref "M7") (pin "9") (pinfunction "9_9") (pintype "passive"))
      (node (ref "M8") (pin "1") (pinfunction "1_1") (pintype "passive"))
      (node (ref "M8") (pin "2") (pinfunction "2_2") (pintype "passive"))
      (node (ref "M8") (pin "3") (pinfunction "3_3") (pintype "passive"))
      (node (ref "M8") (pin "4") (pinfunction "4_4") (pintype "passive"))
      (node (ref "M8") (pin "5") (pinfunction "5_5") (pintype "passive"))
      (node (ref "M8") (pin "6") (pinfunction "6_6") (pintype "passive"))
      (node (ref "M8") (pin "7") (pinfunction "7_7") (pintype "passive"))
      (node (ref "M8") (pin "8") (pinfunction "8_8") (pintype "passive"))
      (node (ref "M8") (pin "9") (pinfunction "9_9") (pintype "passive"))
      (node (ref "M9") (pin "1") (pinfunction "1_1") (pintype "passive"))
      (node (ref "M9") (pin "2") (pinfunction "2_2") (pintype "passive"))
      (node (ref "M9") (pin "3") (pinfunction "3_3") (pintype "passive"))
      (node (ref "M9") (pin "4") (pinfunction "4_4") (pintype "passive"))
      (node (ref "M9") (pin "5") (pinfunction "5_5") (pintype "passive"))
      (node (ref "M9") (pin "6") (pinfunction "6_6") (pintype "passive"))
      (node (ref "M9") (pin "7") (pinfunction "7_7") (pintype "passive"))
      (node (ref "M9") (pin "8") (pinfunction "8_8") (pintype "passive"))
      (node (ref "M9") (pin "9") (pinfunction "9_9") (pintype "passive"))
      (node (ref "P10") (pin "1") (pinfunction "1_1") (pintype "passive"))
      (node (ref "P10") (pin "2") (pinfunction "2_2") (pintype "passive"))
      (node (ref "P10") (pin "39") (pinfunction "39_39") (pintype "passive"))
      (node (ref "P11") (pin "1") (pinfunction "1_1") (pintype "passive"))
      (node (ref "P11") (pin "2") (pinfunction "2_2") (pintype "passive"))
      (node (ref "P11") (pin "39") (pinfunction "39_39") (pintype "passive"))
      (node (ref "P12") (pin "3") (pinfunction "3_3") (pintype "passive"))
      (node (ref "P12") (pin "4") (pinfunction "4_4") (pintype "passive"))
      (node (ref "P3") (pin "1") (pinfunction "1_1") (pintype "passive"))
      (node (ref "P3") (pin "2") (pinfunction "2_2") (pintype "passive"))
      (node (ref "P9") (pin "1") (pinfunction "1_1") (pintype "passive"))
      (node (ref "P9") (pin "2") (pinfunction "2_2") (pintype "passive"))
      (node (ref "P9") (pin "3") (pinfunction "3_3") (pintype "passive"))
      (node (ref "P9") (pin "37") (pinfunction "37_37") (pintype "passive"))
      (node (ref "P9") (pin "38") (pinfunction "38_38") (pintype "passive"))
      (node (ref "P9") (pin "39") (pinfunction "39_39") (pintype "passive"))
      (node (ref "P9") (pin "4") (pinfunction "4_4") (pintype "passive"))
      (node (ref "P9") (pin "40") (pinfunction "40_40") (pintype "passive"))
      (node (ref "Q1") (pin "2") (pinfunction "SOURCE_2") (pintype "passive"))
      (node (ref "Q10") (pin "2") (pinfunction "SOURCE_2") (pintype "passive"))
      (node (ref "Q11") (pin "2") (pinfunction "SOURCE_2") (pintype "passive"))
      (node (ref "Q12") (pin "2") (pinfunction "SOURCE_2") (pintype "passive"))
      (node (ref "Q13") (pin "2") (pinfunction "SOURCE_2") (pintype "passive"))
      (node (ref "Q14") (pin "2") (pinfunction "SOURCE_2") (pintype "passive"))
      (node (ref "Q15") (pin "2") (pinfunction "SOURCE_2") (pintype "passive"))
      (node (ref "Q16") (pin "2") (pinfunction "SOURCE_2") (pintype "passive"))
      (node (ref "Q17") (pin "2") (pinfunction "SOURCE_2") (pintype "passive"))
      (node (ref "Q18") (pin "2") (pinfunction "SOURCE_2") (pintype "passive"))
      (node (ref "Q19") (pin "2") (pinfunction "SOURCE_2") (pintype "passive"))
      (node (ref "Q2") (pin "2") (pinfunction "SOURCE_2") (pintype "passive"))
      (node (ref "Q20") (pin "2") (pinfunction "SOURCE_2") (pintype "passive"))
      (node (ref "Q21") (pin "2") (pinfunction "SOURCE_2") (pintype "passive"))
      (node (ref "Q22") (pin "2") (pinfunction "SOURCE_2") (pintype "passive"))
      (node (ref "Q23") (pin "2") (pinfunction "SOURCE_2") (pintype "passive"))
      (node (ref "Q24") (pin "2") (pinfunction "SOURCE_2") (pintype "passive"))
      (node (ref "Q25") (pin "2") (pinfunction "SOURCE_2") (pintype "passive"))
      (node (ref "Q26") (pin "2") (pinfunction "SOURCE_2") (pintype "passive"))
      (node (ref "Q27") (pin "2") (pinfunction "SOURCE_2") (pintype "passive"))
      (node (ref "Q28") (pin "2") (pinfunction "SOURCE_2") (pintype "passive"))
      (node (ref "Q29") (pin "2") (pinfunction "SOURCE_2") (pintype "passive"))
      (node (ref "Q3") (pin "2") (pinfunction "SOURCE_2") (pintype "passive"))
      (node (ref "Q30") (pin "2") (pinfunction "SOURCE_2") (pintype "passive"))
      (node (ref "Q31") (pin "2") (pinfunction "SOURCE_2") (pintype "passive"))
      (node (ref "Q32") (pin "2") (pinfunction "SOURCE_2") (pintype "passive"))
      (node (ref "Q33") (pin "2") (pinfunction "SOURCE_2") (pintype "passive"))
      (node (ref "Q34") (pin "2") (pinfunction "SOURCE_2") (pintype "passive"))
      (node (ref "Q35") (pin "2") (pinfunction "SOURCE_2") (pintype "passive"))
      (node (ref "Q36") (pin "2") (pinfunction "SOURCE_2") (pintype "passive"))
      (node (ref "Q4") (pin "2") (pinfunction "SOURCE_2") (pintype "passive"))
      (node (ref "Q5") (pin "2") (pinfunction "SOURCE_2") (pintype "passive"))
      (node (ref "Q6") (pin "2") (pinfunction "SOURCE_2") (pintype "passive"))
      (node (ref "Q7") (pin "2") (pinfunction "SOURCE_2") (pintype "passive"))
      (node (ref "Q8") (pin "2") (pinfunction "SOURCE_2") (pintype "passive"))
      (node (ref "Q9") (pin "2") (pinfunction "SOURCE_2") (pintype "passive"))
    )
    (net (code "71") (name "Net-(LD20-A)") (class "Default")
      (node (ref "LD20") (pin "1") (pinfunction "A_1") (pintype "passive"))
      (node (ref "R56") (pin "1") (pinfunction "1_1") (pintype "passive"))
    )
    (net (code "72") (name "Net-(LD20-K)") (class "Default")
      (node (ref "LD20") (pin "2") (pinfunction "K_2") (pintype "passive"))
      (node (ref "Q9") (pin "3") (pinfunction "DRAIN_3") (pintype "passive"))
    )
    (net (code "73") (name "Net-(LD21-A)") (class "Default")
      (node (ref "LD21") (pin "1") (pinfunction "A_1") (pintype "passive"))
      (node (ref "R58") (pin "1") (pinfunction "1_1") (pintype "passive"))
    )
    (net (code "74") (name "Net-(LD21-K)") (class "Default")
      (node (ref "LD21") (pin "2") (pinfunction "K_2") (pintype "passive"))
      (node (ref "Q12") (pin "3") (pinfunction "DRAIN_3") (pintype "passive"))
    )
    (net (code "75") (name "Net-(LD22-A)") (class "Default")
      (node (ref "LD22") (pin "1") (pinfunction "A_1") (pintype "passive"))
      (node (ref "R60") (pin "1") (pinfunction "1_1") (pintype "passive"))
    )
    (net (code "76") (name "Net-(LD22-K)") (class "Default")
      (node (ref "LD22") (pin "2") (pinfunction "K_2") (pintype "passive"))
      (node (ref "Q15") (pin "3") (pinfunction "DRAIN_3") (pintype "passive"))
    )
    (net (code "77") (name "Net-(LD23-A)") (class "Default")
      (node (ref "LD23") (pin "1") (pinfunction "A_1") (pintype "passive"))
      (node (ref "R62") (pin "1") (pinfunction "1_1") (pintype "passive"))
    )
    (net (code "78") (name "Net-(LD23-K)") (class "Default")
      (node (ref "LD23") (pin "2") (pinfunction "K_2") (pintype "passive"))
      (node (ref "Q18") (pin "3") (pinfunction "DRAIN_3") (pintype "passive"))
    )
    (net (code "79") (name "Net-(LD24-A)") (class "Default")
      (node (ref "LD24") (pin "1") (pinfunction "A_1") (pintype "passive"))
      (node (ref "R64") (pin "1") (pinfunction "1_1") (pintype "passive"))
    )
    (net (code "80") (name "Net-(LD24-K)") (class "Default")
      (node (ref "LD24") (pin "2") (pinfunction "K_2") (pintype "passive"))
      (node (ref "Q21") (pin "3") (pinfunction "DRAIN_3") (pintype "passive"))
    )
    (net (code "81") (name "Net-(LD25-A)") (class "Default")
      (node (ref "LD25") (pin "1") (pinfunction "A_1") (pintype "passive"))
      (node (ref "R66") (pin "1") (pinfunction "1_1") (pintype "passive"))
    )
    (net (code "82") (name "Net-(LD25-K)") (class "Default")
      (node (ref "LD25") (pin "2") (pinfunction "K_2") (pintype "passive"))
      (node (ref "Q24") (pin "3") (pinfunction "DRAIN_3") (pintype "passive"))
    )
    (net (code "83") (name "Net-(LD26-A)") (class "Default")
      (node (ref "LD26") (pin "1") (pinfunction "A_1") (pintype "passive"))
      (node (ref "R68") (pin "1") (pinfunction "1_1") (pintype "passive"))
    )
    (net (code "84") (name "Net-(LD26-K)") (class "Default")
      (node (ref "LD26") (pin "2") (pinfunction "K_2") (pintype "passive"))
      (node (ref "Q27") (pin "3") (pinfunction "DRAIN_3") (pintype "passive"))
    )
    (net (code "85") (name "Net-(LD27-A)") (class "Default")
      (node (ref "LD27") (pin "1") (pinfunction "A_1") (pintype "passive"))
      (node (ref "R70") (pin "1") (pinfunction "1_1") (pintype "passive"))
    )
    (net (code "86") (name "Net-(LD27-K)") (class "Default")
      (node (ref "LD27") (pin "2") (pinfunction "K_2") (pintype "passive"))
      (node (ref "Q29") (pin "3") (pinfunction "DRAIN_3") (pintype "passive"))
    )
    (net (code "87") (name "Net-(LD28-A)") (class "Default")
      (node (ref "LD28") (pin "1") (pinfunction "A_1") (pintype "passive"))
      (node (ref "R72") (pin "1") (pinfunction "1_1") (pintype "passive"))
    )
    (net (code "88") (name "Net-(LD28-K)") (class "Default")
      (node (ref "LD28") (pin "2") (pinfunction "K_2") (pintype "passive"))
      (node (ref "Q31") (pin "3") (pinfunction "DRAIN_3") (pintype "passive"))
    )
    (net (code "89") (name "Net-(LD29-A)") (class "Default")
      (node (ref "LD29") (pin "1") (pinfunction "A_1") (pintype "passive"))
      (node (ref "R74") (pin "1") (pinfunction "1_1") (pintype "passive"))
    )
    (net (code "90") (name "Net-(LD29-K)") (class "Default")
      (node (ref "LD29") (pin "2") (pinfunction "K_2") (pintype "passive"))
      (node (ref "Q33") (pin "3") (pinfunction "DRAIN_3") (pintype "passive"))
    )
    (net (code "91") (name "Net-(LD30-A)") (class "Default")
      (node (ref "LD30") (pin "1") (pinfunction "A_1") (pintype "passive"))
      (node (ref "R76") (pin "1") (pinfunction "1_1") (pintype "passive"))
    )
    (net (code "92") (name "Net-(LD30-K)") (class "Default")
      (node (ref "LD30") (pin "2") (pinfunction "K_2") (pintype "passive"))
      (node (ref "Q35") (pin "3") (pinfunction "DRAIN_3") (pintype "passive"))
    )
    (net (code "93") (name "Net-(LD31-A)") (class "Default")
      (node (ref "LD31") (pin "1") (pinfunction "A_1") (pintype "passive"))
      (node (ref "R78") (pin "1") (pinfunction "1_1") (pintype "passive"))
    )
    (net (code "94") (name "Net-(LD31-K)") (class "Default")
      (node (ref "LD31") (pin "2") (pinfunction "K_2") (pintype "passive"))
      (node (ref "Q1") (pin "3") (pinfunction "DRAIN_3") (pintype "passive"))
    )
    (net (code "95") (name "Net-(LD32-A)") (class "Default")
      (node (ref "LD32") (pin "1") (pinfunction "A_1") (pintype "passive"))
      (node (ref "R80") (pin "1") (pinfunction "1_1") (pintype "passive"))
    )
    (net (code "96") (name "Net-(LD32-K)") (class "Default")
      (node (ref "LD32") (pin "2") (pinfunction "K_2") (pintype "passive"))
      (node (ref "Q3") (pin "3") (pinfunction "DRAIN_3") (pintype "passive"))
    )
    (net (code "97") (name "Net-(LD33-A)") (class "Default")
      (node (ref "LD33") (pin "1") (pinfunction "A_1") (pintype "passive"))
      (node (ref "R82") (pin "1") (pinfunction "1_1") (pintype "passive"))
    )
    (net (code "98") (name "Net-(LD33-K)") (class "Default")
      (node (ref "LD33") (pin "2") (pinfunction "K_2") (pintype "passive"))
      (node (ref "Q5") (pin "3") (pinfunction "DRAIN_3") (pintype "passive"))
    )
    (net (code "99") (name "Net-(LD34-A)") (class "Default")
      (node (ref "LD34") (pin "1") (pinfunction "A_1") (pintype "passive"))
      (node (ref "R84") (pin "1") (pinfunction "1_1") (pintype "passive"))
    )
    (net (code "100") (name "Net-(LD34-K)") (class "Default")
      (node (ref "LD34") (pin "2") (pinfunction "K_2") (pintype "passive"))
      (node (ref "Q7") (pin "3") (pinfunction "DRAIN_3") (pintype "passive"))
    )
    (net (code "101") (name "Net-(LD35-A)") (class "Default")
      (node (ref "LD35") (pin "1") (pinfunction "A_1") (pintype "passive"))
      (node (ref "R86") (pin "1") (pinfunction "1_1") (pintype "passive"))
    )
    (net (code "102") (name "Net-(LD35-K)") (class "Default")
      (node (ref "LD35") (pin "2") (pinfunction "K_2") (pintype "passive"))
      (node (ref "Q10") (pin "3") (pinfunction "DRAIN_3") (pintype "passive"))
    )
    (net (code "103") (name "Net-(LD36-A)") (class "Default")
      (node (ref "LD36") (pin "1") (pinfunction "A_1") (pintype "passive"))
      (node (ref "R88") (pin "1") (pinfunction "1_1") (pintype "passive"))
    )
    (net (code "104") (name "Net-(LD36-K)") (class "Default")
      (node (ref "LD36") (pin "2") (pinfunction "K_2") (pintype "passive"))
      (node (ref "Q13") (pin "3") (pinfunction "DRAIN_3") (pintype "passive"))
    )
    (net (code "105") (name "Net-(LD37-A)") (class "Default")
      (node (ref "LD37") (pin "1") (pinfunction "A_1") (pintype "passive"))
      (node (ref "R90") (pin "1") (pinfunction "1_1") (pintype "passive"))
    )
    (net (code "106") (name "Net-(LD37-K)") (class "Default")
      (node (ref "LD37") (pin "2") (pinfunction "K_2") (pintype "passive"))
      (node (ref "Q16") (pin "3") (pinfunction "DRAIN_3") (pintype "passive"))
    )
    (net (code "107") (name "Net-(LD38-A)") (class "Default")
      (node (ref "LD38") (pin "1") (pinfunction "A_1") (pintype "passive"))
      (node (ref "R92") (pin "1") (pinfunction "1_1") (pintype "passive"))
    )
    (net (code "108") (name "Net-(LD38-K)") (class "Default")
      (node (ref "LD38") (pin "2") (pinfunction "K_2") (pintype "passive"))
      (node (ref "Q19") (pin "3") (pinfunction "DRAIN_3") (pintype "passive"))
    )
    (net (code "109") (name "Net-(LD39-A)") (class "Default")
      (node (ref "LD39") (pin "1") (pinfunction "A_1") (pintype "passive"))
      (node (ref "R94") (pin "1") (pinfunction "1_1") (pintype "passive"))
    )
    (net (code "110") (name "Net-(LD39-K)") (class "Default")
      (node (ref "LD39") (pin "2") (pinfunction "K_2") (pintype "passive"))
      (node (ref "Q22") (pin "3") (pinfunction "DRAIN_3") (pintype "passive"))
    )
    (net (code "111") (name "Net-(LD40-A)") (class "Default")
      (node (ref "LD40") (pin "1") (pinfunction "A_1") (pintype "passive"))
      (node (ref "R96") (pin "1") (pinfunction "1_1") (pintype "passive"))
    )
    (net (code "112") (name "Net-(LD40-K)") (class "Default")
      (node (ref "LD40") (pin "2") (pinfunction "K_2") (pintype "passive"))
      (node (ref "Q25") (pin "3") (pinfunction "DRAIN_3") (pintype "passive"))
    )
    (net (code "113") (name "Net-(LD41-A)") (class "Default")
      (node (ref "LD41") (pin "1") (pinfunction "A_1") (pintype "passive"))
      (node (ref "R98") (pin "1") (pinfunction "1_1") (pintype "passive"))
    )
    (net (code "114") (name "Net-(LD41-K)") (class "Default")
      (node (ref "LD41") (pin "2") (pinfunction "K_2") (pintype "passive"))
      (node (ref "Q28") (pin "3") (pinfunction "DRAIN_3") (pintype "passive"))
    )
    (net (code "115") (name "Net-(LD42-A)") (class "Default")
      (node (ref "LD42") (pin "1") (pinfunction "A_1") (pintype "passive"))
      (node (ref "R100") (pin "1") (pinfunction "1_1") (pintype "passive"))
    )
    (net (code "116") (name "Net-(LD42-K)") (class "Default")
      (node (ref "LD42") (pin "2") (pinfunction "K_2") (pintype "passive"))
      (node (ref "Q30") (pin "3") (pinfunction "DRAIN_3") (pintype "passive"))
    )
    (net (code "117") (name "Net-(LD43-A)") (class "Default")
      (node (ref "LD43") (pin "1") (pinfunction "A_1") (pintype "passive"))
      (node (ref "R102") (pin "1") (pinfunction "1_1") (pintype "passive"))
    )
    (net (code "118") (name "Net-(LD43-K)") (class "Default")
      (node (ref "LD43") (pin "2") (pinfunction "K_2") (pintype "passive"))
      (node (ref "Q32") (pin "3") (pinfunction "DRAIN_3") (pintype "passive"))
    )
    (net (code "119") (name "Net-(LD44-A)") (class "Default")
      (node (ref "LD44") (pin "1") (pinfunction "A_1") (pintype "passive"))
      (node (ref "R104") (pin "1") (pinfunction "1_1") (pintype "passive"))
    )
    (net (code "120") (name "Net-(LD44-K)") (class "Default")
      (node (ref "LD44") (pin "2") (pinfunction "K_2") (pintype "passive"))
      (node (ref "Q34") (pin "3") (pinfunction "DRAIN_3") (pintype "passive"))
    )
    (net (code "121") (name "Net-(LD45-A)") (class "Default")
      (node (ref "LD45") (pin "1") (pinfunction "A_1") (pintype "passive"))
      (node (ref "R106") (pin "1") (pinfunction "1_1") (pintype "passive"))
    )
    (net (code "122") (name "Net-(LD45-K)") (class "Default")
      (node (ref "LD45") (pin "2") (pinfunction "K_2") (pintype "passive"))
      (node (ref "Q36") (pin "3") (pinfunction "DRAIN_3") (pintype "passive"))
    )
    (net (code "123") (name "Net-(LD46-A)") (class "Default")
      (node (ref "LD46") (pin "1") (pinfunction "A_1") (pintype "passive"))
      (node (ref "R108") (pin "1") (pinfunction "1_1") (pintype "passive"))
    )
    (net (code "124") (name "Net-(LD46-K)") (class "Default")
      (node (ref "LD46") (pin "2") (pinfunction "K_2") (pintype "passive"))
      (node (ref "Q2") (pin "3") (pinfunction "DRAIN_3") (pintype "passive"))
    )
    (net (code "125") (name "Net-(LD47-A)") (class "Default")
      (node (ref "LD47") (pin "1") (pinfunction "A_1") (pintype "passive"))
      (node (ref "R110") (pin "1") (pinfunction "1_1") (pintype "passive"))
    )
    (net (code "126") (name "Net-(LD47-K)") (class "Default")
      (node (ref "LD47") (pin "2") (pinfunction "K_2") (pintype "passive"))
      (node (ref "Q4") (pin "3") (pinfunction "DRAIN_3") (pintype "passive"))
    )
    (net (code "127") (name "Net-(LD48-A)") (class "Default")
      (node (ref "LD48") (pin "1") (pinfunction "A_1") (pintype "passive"))
      (node (ref "R112") (pin "1") (pinfunction "1_1") (pintype "passive"))
    )
    (net (code "128") (name "Net-(LD48-K)") (class "Default")
      (node (ref "LD48") (pin "2") (pinfunction "K_2") (pintype "passive"))
      (node (ref "Q6") (pin "3") (pinfunction "DRAIN_3") (pintype "passive"))
    )
    (net (code "129") (name "Net-(LD49-A)") (class "Default")
      (node (ref "LD49") (pin "1") (pinfunction "A_1") (pintype "passive"))
      (node (ref "R114") (pin "1") (pinfunction "1_1") (pintype "passive"))
    )
    (net (code "130") (name "Net-(LD49-K)") (class "Default")
      (node (ref "LD49") (pin "2") (pinfunction "K_2") (pintype "passive"))
      (node (ref "Q8") (pin "3") (pinfunction "DRAIN_3") (pintype "passive"))
    )
    (net (code "131") (name "Net-(LD50-A)") (class "Default")
      (node (ref "LD50") (pin "1") (pinfunction "A_1") (pintype "passive"))
      (node (ref "R116") (pin "1") (pinfunction "1_1") (pintype "passive"))
    )
    (net (code "132") (name "Net-(LD50-K)") (class "Default")
      (node (ref "LD50") (pin "2") (pinfunction "K_2") (pintype "passive"))
      (node (ref "Q11") (pin "3") (pinfunction "DRAIN_3") (pintype "passive"))
    )
    (net (code "133") (name "Net-(LD51-A)") (class "Default")
      (node (ref "LD51") (pin "1") (pinfunction "A_1") (pintype "passive"))
      (node (ref "R118") (pin "1") (pinfunction "1_1") (pintype "passive"))
    )
    (net (code "134") (name "Net-(LD51-K)") (class "Default")
      (node (ref "LD51") (pin "2") (pinfunction "K_2") (pintype "passive"))
      (node (ref "Q14") (pin "3") (pinfunction "DRAIN_3") (pintype "passive"))
    )
    (net (code "135") (name "Net-(LD52-A)") (class "Default")
      (node (ref "LD52") (pin "1") (pinfunction "A_1") (pintype "passive"))
      (node (ref "R120") (pin "1") (pinfunction "1_1") (pintype "passive"))
    )
    (net (code "136") (name "Net-(LD52-K)") (class "Default")
      (node (ref "LD52") (pin "2") (pinfunction "K_2") (pintype "passive"))
      (node (ref "Q17") (pin "3") (pinfunction "DRAIN_3") (pintype "passive"))
    )
    (net (code "137") (name "Net-(LD53-A)") (class "Default")
      (node (ref "LD53") (pin "1") (pinfunction "A_1") (pintype "passive"))
      (node (ref "R122") (pin "1") (pinfunction "1_1") (pintype "passive"))
    )
    (net (code "138") (name "Net-(LD53-K)") (class "Default")
      (node (ref "LD53") (pin "2") (pinfunction "K_2") (pintype "passive"))
      (node (ref "Q20") (pin "3") (pinfunction "DRAIN_3") (pintype "passive"))
    )
    (net (code "139") (name "Net-(LD54-A)") (class "Default")
      (node (ref "LD54") (pin "1") (pinfunction "A_1") (pintype "passive"))
      (node (ref "R124") (pin "1") (pinfunction "1_1") (pintype "passive"))
    )
    (net (code "140") (name "Net-(LD54-K)") (class "Default")
      (node (ref "LD54") (pin "2") (pinfunction "K_2") (pintype "passive"))
      (node (ref "Q23") (pin "3") (pinfunction "DRAIN_3") (pintype "passive"))
    )
    (net (code "141") (name "Net-(LD55-A)") (class "Default")
      (node (ref "LD55") (pin "1") (pinfunction "A_1") (pintype "passive"))
      (node (ref "R126") (pin "1") (pinfunction "1_1") (pintype "passive"))
    )
    (net (code "142") (name "Net-(LD55-K)") (class "Default")
      (node (ref "LD55") (pin "2") (pinfunction "K_2") (pintype "passive"))
      (node (ref "Q26") (pin "3") (pinfunction "DRAIN_3") (pintype "passive"))
    )
    (net (code "143") (name "Net-(Q1-GATE)") (class "Default")
      (node (ref "Q1") (pin "1") (pinfunction "GATE_1") (pintype "passive"))
      (node (ref "R79") (pin "1") (pinfunction "1_1") (pintype "passive"))
    )
    (net (code "144") (name "Net-(Q2-GATE)") (class "Default")
      (node (ref "Q2") (pin "1") (pinfunction "GATE_1") (pintype "passive"))
      (node (ref "R109") (pin "1") (pinfunction "1_1") (pintype "passive"))
    )
    (net (code "145") (name "Net-(Q3-GATE)") (class "Default")
      (node (ref "Q3") (pin "1") (pinfunction "GATE_1") (pintype "passive"))
      (node (ref "R81") (pin "1") (pinfunction "1_1") (pintype "passive"))
    )
    (net (code "146") (name "Net-(Q4-GATE)") (class "Default")
      (node (ref "Q4") (pin "1") (pinfunction "GATE_1") (pintype "passive"))
      (node (ref "R111") (pin "1") (pinfunction "1_1") (pintype "passive"))
    )
    (net (code "147") (name "Net-(Q5-GATE)") (class "Default")
      (node (ref "Q5") (pin "1") (pinfunction "GATE_1") (pintype "passive"))
      (node (ref "R83") (pin "1") (pinfunction "1_1") (pintype "passive"))
    )
    (net (code "148") (name "Net-(Q6-GATE)") (class "Default")
      (node (ref "Q6") (pin "1") (pinfunction "GATE_1") (pintype "passive"))
      (node (ref "R113") (pin "1") (pinfunction "1_1") (pintype "passive"))
    )
    (net (code "149") (name "Net-(Q7-GATE)") (class "Default")
      (node (ref "Q7") (pin "1") (pinfunction "GATE_1") (pintype "passive"))
      (node (ref "R85") (pin "1") (pinfunction "1_1") (pintype "passive"))
    )
    (net (code "150") (name "Net-(Q8-GATE)") (class "Default")
      (node (ref "Q8") (pin "1") (pinfunction "GATE_1") (pintype "passive"))
      (node (ref "R115") (pin "1") (pinfunction "1_1") (pintype "passive"))
    )
    (net (code "151") (name "Net-(Q9-GATE)") (class "Default")
      (node (ref "Q9") (pin "1") (pinfunction "GATE_1") (pintype "passive"))
      (node (ref "R57") (pin "1") (pinfunction "1_1") (pintype "passive"))
    )
    (net (code "152") (name "Net-(Q10-GATE)") (class "Default")
      (node (ref "Q10") (pin "1") (pinfunction "GATE_1") (pintype "passive"))
      (node (ref "R87") (pin "1") (pinfunction "1_1") (pintype "passive"))
    )
    (net (code "153") (name "Net-(Q11-GATE)") (class "Default")
      (node (ref "Q11") (pin "1") (pinfunction "GATE_1") (pintype "passive"))
      (node (ref "R117") (pin "1") (pinfunction "1_1") (pintype "passive"))
    )
    (net (code "154") (name "Net-(Q12-GATE)") (class "Default")
      (node (ref "Q12") (pin "1") (pinfunction "GATE_1") (pintype "passive"))
      (node (ref "R59") (pin "1") (pinfunction "1_1") (pintype "passive"))
    )
    (net (code "155") (name "Net-(Q13-GATE)") (class "Default")
      (node (ref "Q13") (pin "1") (pinfunction "GATE_1") (pintype "passive"))
      (node (ref "R89") (pin "1") (pinfunction "1_1") (pintype "passive"))
    )
    (net (code "156") (name "Net-(Q14-GATE)") (class "Default")
      (node (ref "Q14") (pin "1") (pinfunction "GATE_1") (pintype "passive"))
      (node (ref "R119") (pin "1") (pinfunction "1_1") (pintype "passive"))
    )
    (net (code "157") (name "Net-(Q15-GATE)") (class "Default")
      (node (ref "Q15") (pin "1") (pinfunction "GATE_1") (pintype "passive"))
      (node (ref "R61") (pin "1") (pinfunction "1_1") (pintype "passive"))
    )
    (net (code "158") (name "Net-(Q16-GATE)") (class "Default")
      (node (ref "Q16") (pin "1") (pinfunction "GATE_1") (pintype "passive"))
      (node (ref "R91") (pin "1") (pinfunction "1_1") (pintype "passive"))
    )
    (net (code "159") (name "Net-(Q17-GATE)") (class "Default")
      (node (ref "Q17") (pin "1") (pinfunction "GATE_1") (pintype "passive"))
      (node (ref "R121") (pin "1") (pinfunction "1_1") (pintype "passive"))
    )
    (net (code "160") (name "Net-(Q18-GATE)") (class "Default")
      (node (ref "Q18") (pin "1") (pinfunction "GATE_1") (pintype "passive"))
      (node (ref "R63") (pin "1") (pinfunction "1_1") (pintype "passive"))
    )
    (net (code "161") (name "Net-(Q19-GATE)") (class "Default")
      (node (ref "Q19") (pin "1") (pinfunction "GATE_1") (pintype "passive"))
      (node (ref "R93") (pin "1") (pinfunction "1_1") (pintype "passive"))
    )
    (net (code "162") (name "Net-(Q20-GATE)") (class "Default")
      (node (ref "Q20") (pin "1") (pinfunction "GATE_1") (pintype "passive"))
      (node (ref "R123") (pin "1") (pinfunction "1_1") (pintype "passive"))
    )
    (net (code "163") (name "Net-(Q21-GATE)") (class "Default")
      (node (ref "Q21") (pin "1") (pinfunction "GATE_1") (pintype "passive"))
      (node (ref "R65") (pin "1") (pinfunction "1_1") (pintype "passive"))
    )
    (net (code "164") (name "Net-(Q22-GATE)") (class "Default")
      (node (ref "Q22") (pin "1") (pinfunction "GATE_1") (pintype "passive"))
      (node (ref "R95") (pin "1") (pinfunction "1_1") (pintype "passive"))
    )
    (net (code "165") (name "Net-(Q23-GATE)") (class "Default")
      (node (ref "Q23") (pin "1") (pinfunction "GATE_1") (pintype "passive"))
      (node (ref "R125") (pin "1") (pinfunction "1_1") (pintype "passive"))
    )
    (net (code "166") (name "Net-(Q24-GATE)") (class "Default")
      (node (ref "Q24") (pin "1") (pinfunction "GATE_1") (pintype "passive"))
      (node (ref "R67") (pin "1") (pinfunction "1_1") (pintype "passive"))
    )
    (net (code "167") (name "Net-(Q25-GATE)") (class "Default")
      (node (ref "Q25") (pin "1") (pinfunction "GATE_1") (pintype "passive"))
      (node (ref "R97") (pin "1") (pinfunction "1_1") (pintype "passive"))
    )
    (net (code "168") (name "Net-(Q26-GATE)") (class "Default")
      (node (ref "Q26") (pin "1") (pinfunction "GATE_1") (pintype "passive"))
      (node (ref "R127") (pin "1") (pinfunction "1_1") (pintype "passive"))
    )
    (net (code "169") (name "Net-(Q27-GATE)") (class "Default")
      (node (ref "Q27") (pin "1") (pinfunction "GATE_1") (pintype "passive"))
      (node (ref "R69") (pin "1") (pinfunction "1_1") (pintype "passive"))
    )
    (net (code "170") (name "Net-(Q28-GATE)") (class "Default")
      (node (ref "Q28") (pin "1") (pinfunction "GATE_1") (pintype "passive"))
      (node (ref "R99") (pin "1") (pinfunction "1_1") (pintype "passive"))
    )
    (net (code "171") (name "Net-(Q29-GATE)") (class "Default")
      (node (ref "Q29") (pin "1") (pinfunction "GATE_1") (pintype "passive"))
      (node (ref "R71") (pin "1") (pinfunction "1_1") (pintype "passive"))
    )
    (net (code "172") (name "Net-(Q30-GATE)") (class "Default")
      (node (ref "Q30") (pin "1") (pinfunction "GATE_1") (pintype "passive"))
      (node (ref "R101") (pin "1") (pinfunction "1_1") (pintype "passive"))
    )
    (net (code "173") (name "Net-(Q31-GATE)") (class "Default")
      (node (ref "Q31") (pin "1") (pinfunction "GATE_1") (pintype "passive"))
      (node (ref "R73") (pin "1") (pinfunction "1_1") (pintype "passive"))
    )
    (net (code "174") (name "Net-(Q32-GATE)") (class "Default")
      (node (ref "Q32") (pin "1") (pinfunction "GATE_1") (pintype "passive"))
      (node (ref "R103") (pin "1") (pinfunction "1_1") (pintype "passive"))
    )
    (net (code "175") (name "Net-(Q33-GATE)") (class "Default")
      (node (ref "Q33") (pin "1") (pinfunction "GATE_1") (pintype "passive"))
      (node (ref "R75") (pin "1") (pinfunction "1_1") (pintype "passive"))
    )
    (net (code "176") (name "Net-(Q34-GATE)") (class "Default")
      (node (ref "Q34") (pin "1") (pinfunction "GATE_1") (pintype "passive"))
      (node (ref "R105") (pin "1") (pinfunction "1_1") (pintype "passive"))
    )
    (net (code "177") (name "Net-(Q35-GATE)") (class "Default")
      (node (ref "Q35") (pin "1") (pinfunction "GATE_1") (pintype "passive"))
      (node (ref "R77") (pin "1") (pinfunction "1_1") (pintype "passive"))
    )
    (net (code "178") (name "Net-(Q36-GATE)") (class "Default")
      (node (ref "Q36") (pin "1") (pinfunction "GATE_1") (pintype "passive"))
      (node (ref "R107") (pin "1") (pinfunction "1_1") (pintype "passive"))
    )
    (net (code "179") (name "VCC2.5") (class "Default")
      (node (ref "C29") (pin "1") (pintype "passive"))
      (node (ref "C30") (pin "2") (pintype "passive"))
      (node (ref "P12") (pin "1") (pinfunction "1_1") (pintype "passive"))
      (node (ref "P12") (pin "2") (pinfunction "2_2") (pintype "passive"))
      (node (ref "P3") (pin "3") (pinfunction "3_3") (pintype "passive"))
      (node (ref "P3") (pin "4") (pinfunction "4_4") (pintype "passive"))
      (node (ref "R100") (pin "2") (pinfunction "2_2") (pintype "passive"))
      (node (ref "R102") (pin "2") (pinfunction "2_2") (pintype "passive"))
      (node (ref "R104") (pin "2") (pinfunction "2_2") (pintype "passive"))
      (node (ref "R106") (pin "2") (pinfunction "2_2") (pintype "passive"))
      (node (ref "R108") (pin "2") (pinfunction "2_2") (pintype "passive"))
      (node (ref "R110") (pin "2") (pinfunction "2_2") (pintype "passive"))
      (node (ref "R112") (pin "2") (pinfunction "2_2") (pintype "passive"))
      (node (ref "R114") (pin "2") (pinfunction "2_2") (pintype "passive"))
      (node (ref "R116") (pin "2") (pinfunction "2_2") (pintype "passive"))
      (node (ref "R118") (pin "2") (pinfunction "2_2") (pintype "passive"))
      (node (ref "R120") (pin "2") (pinfunction "2_2") (pintype "passive"))
      (node (ref "R122") (pin "2") (pinfunction "2_2") (pintype "passive"))
      (node (ref "R124") (pin "2") (pinfunction "2_2") (pintype "passive"))
      (node (ref "R126") (pin "2") (pinfunction "2_2") (pintype "passive"))
      (node (ref "R56") (pin "2") (pinfunction "2_2") (pintype "passive"))
      (node (ref "R58") (pin "2") (pinfunction "2_2") (pintype "passive"))
      (node (ref "R60") (pin "2") (pinfunction "2_2") (pintype "passive"))
      (node (ref "R62") (pin "2") (pinfunction "2_2") (pintype "passive"))
      (node (ref "R64") (pin "2") (pinfunction "2_2") (pintype "passive"))
      (node (ref "R66") (pin "2") (pinfunction "2_2") (pintype "passive"))
      (node (ref "R68") (pin "2") (pinfunction "2_2") (pintype "passive"))
      (node (ref "R70") (pin "2") (pinfunction "2_2") (pintype "passive"))
      (node (ref "R72") (pin "2") (pinfunction "2_2") (pintype "passive"))
      (node (ref "R74") (pin "2") (pinfunction "2_2") (pintype "passive"))
      (node (ref "R76") (pin "2") (pinfunction "2_2") (pintype "passive"))
      (node (ref "R78") (pin "2") (pinfunction "2_2") (pintype "passive"))
      (node (ref "R80") (pin "2") (pinfunction "2_2") (pintype "passive"))
      (node (ref "R82") (pin "2") (pinfunction "2_2") (pintype "passive"))
      (node (ref "R84") (pin "2") (pinfunction "2_2") (pintype "passive"))
      (node (ref "R86") (pin "2") (pinfunction "2_2") (pintype "passive"))
      (node (ref "R88") (pin "2") (pinfunction "2_2") (pintype "passive"))
      (node (ref "R90") (pin "2") (pinfunction "2_2") (pintype "passive"))
      (node (ref "R92") (pin "2") (pinfunction "2_2") (pintype "passive"))
      (node (ref "R94") (pin "2") (pinfunction "2_2") (pintype "passive"))
      (node (ref "R96") (pin "2") (pinfunction "2_2") (pintype "passive"))
      (node (ref "R98") (pin "2") (pinfunction "2_2") (pintype "passive"))
    )
    (net (code "180") (name "unconnected-(P11-Pad3)") (class "Default")
      (node (ref "P11") (pin "3") (pinfunction "3_3") (pintype "passive"))
    )
    (net (code "181") (name "unconnected-(P11-Pad5)") (class "Default")
      (node (ref "P11") (pin "5") (pinfunction "5_5") (pintype "passive"))
    )
    (net (code "182") (name "unconnected-(P11-Pad7)") (class "Default")
      (node (ref "P11") (pin "7") (pinfunction "7_7") (pintype "passive"))
    )
    (net (code "183") (name "unconnected-(P11-Pad9)") (class "Default")
      (node (ref "P11") (pin "9") (pinfunction "9_9") (pintype "passive"))
    )
  )
)
